# CESC16_copy_copy.net
KiCad netlist of a schematic drawn in EasyEDA
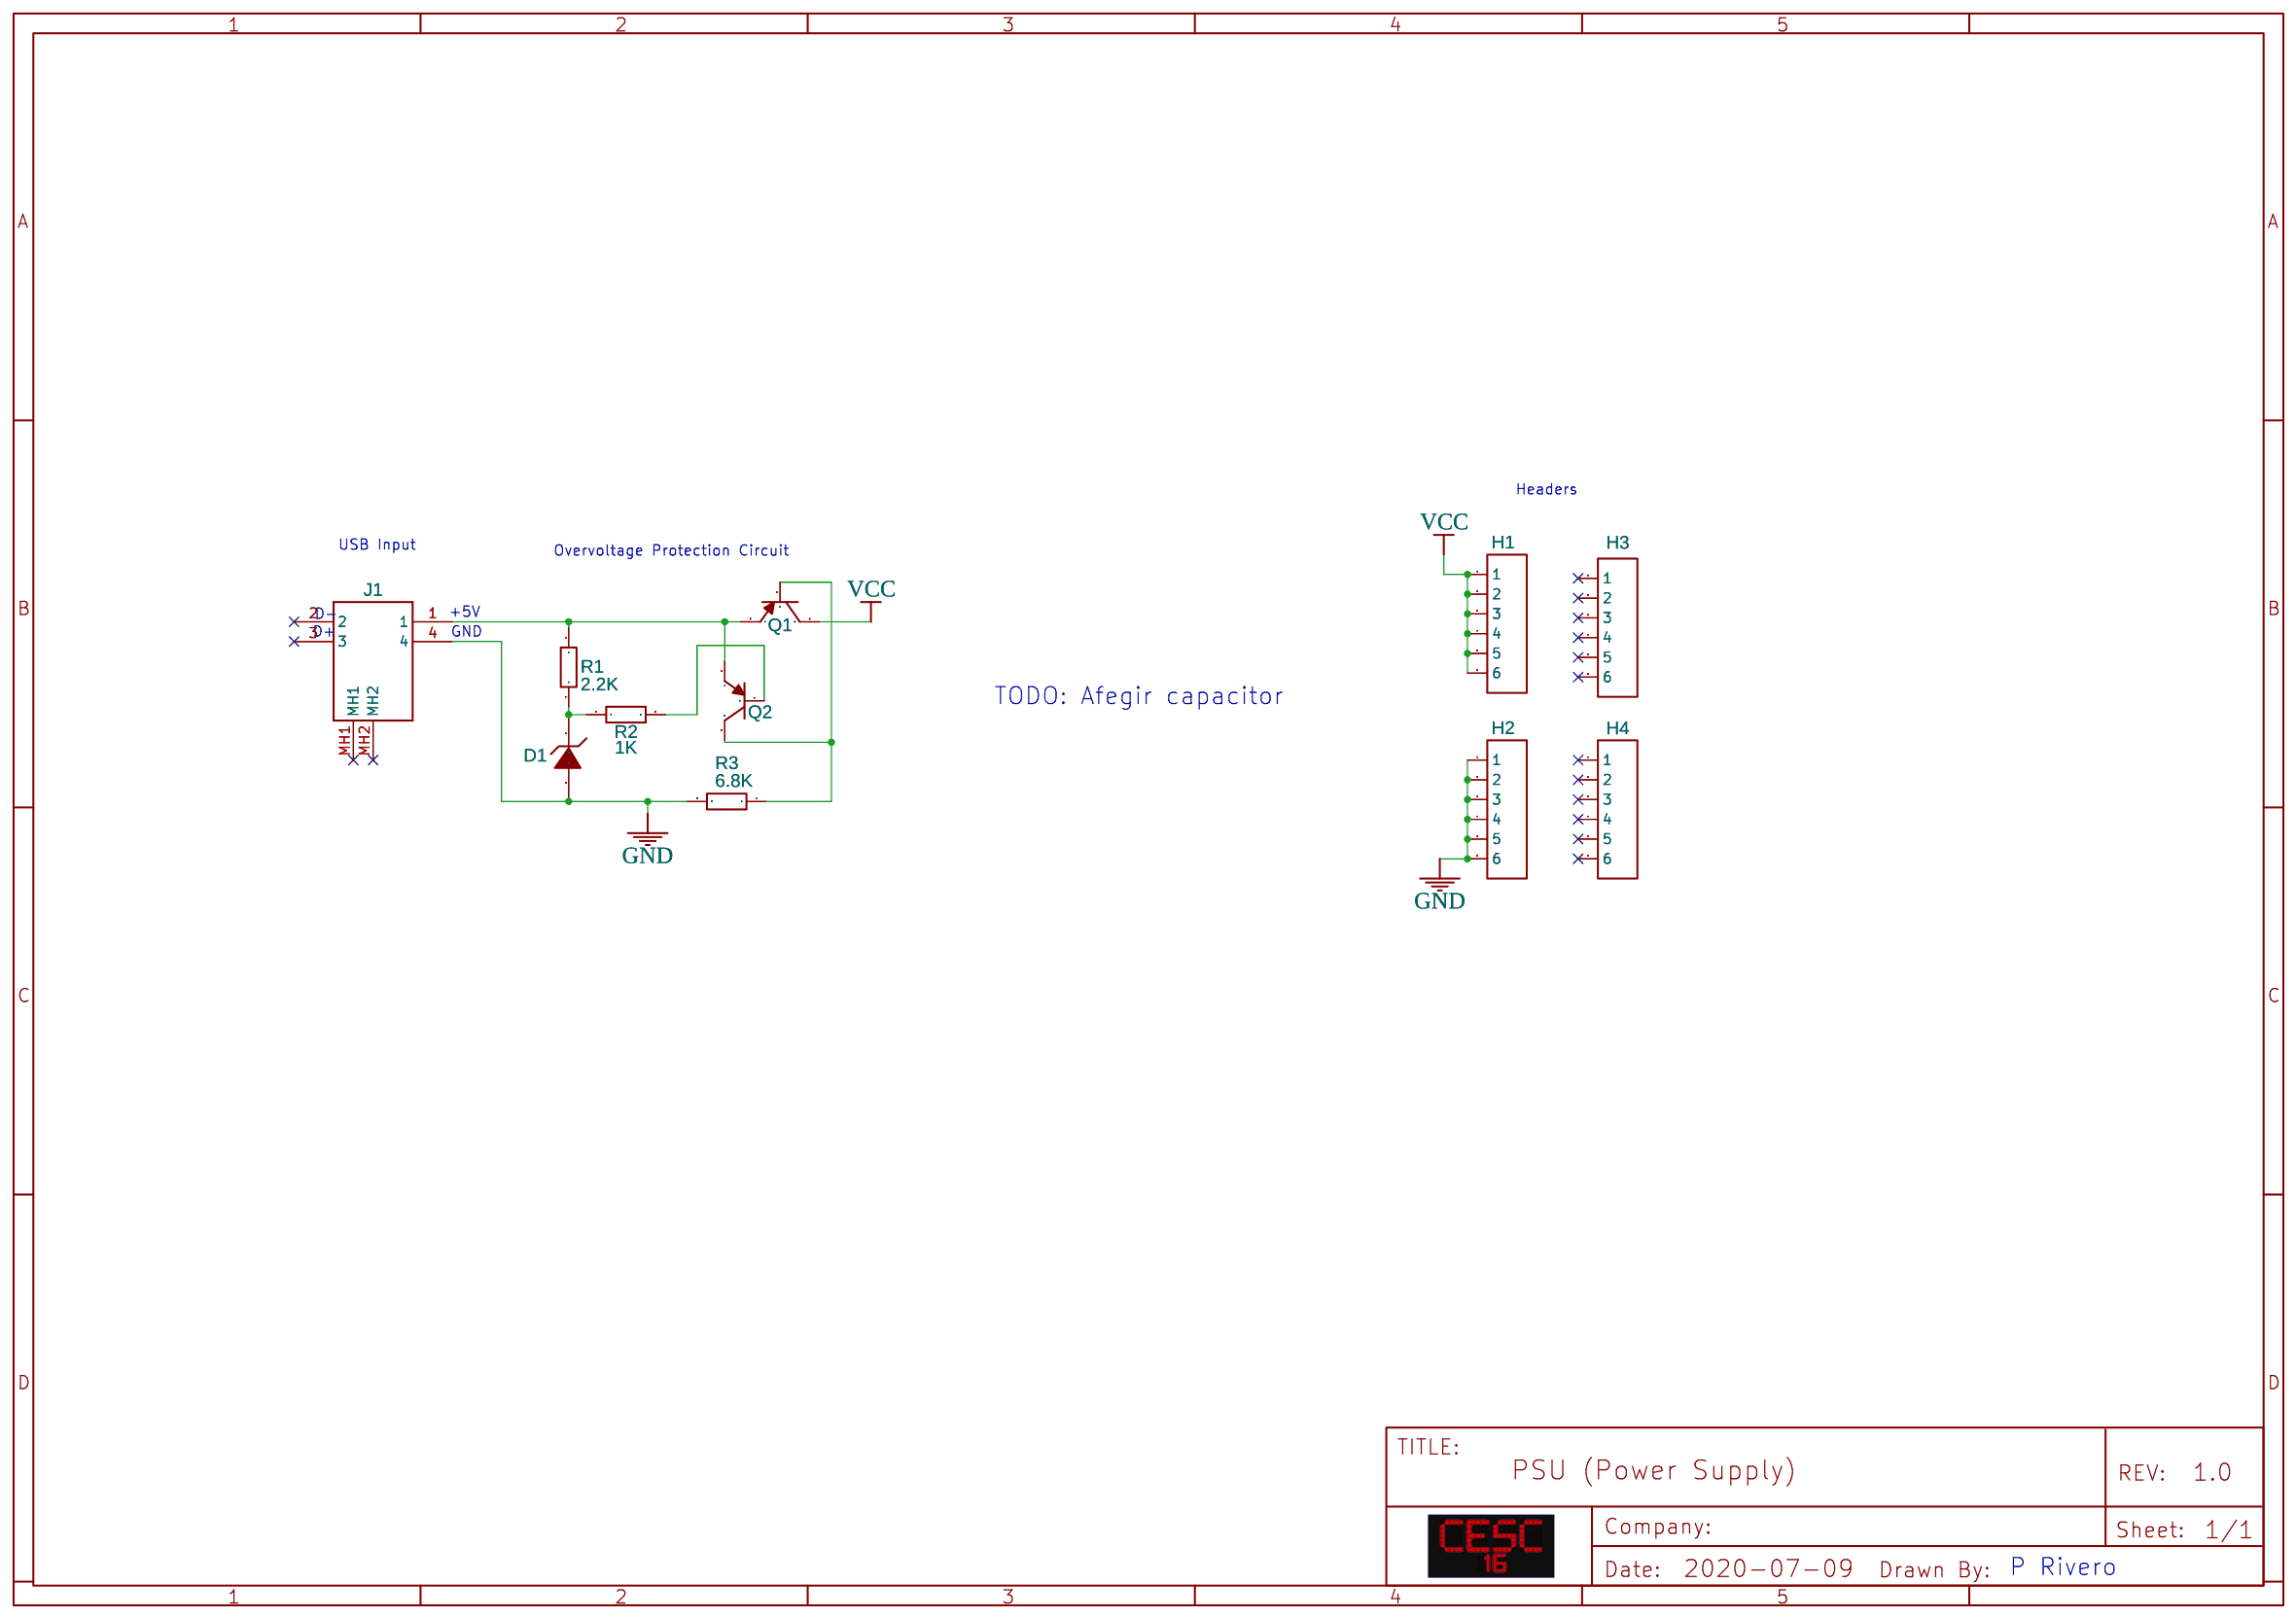
[diagram p0: PSU]
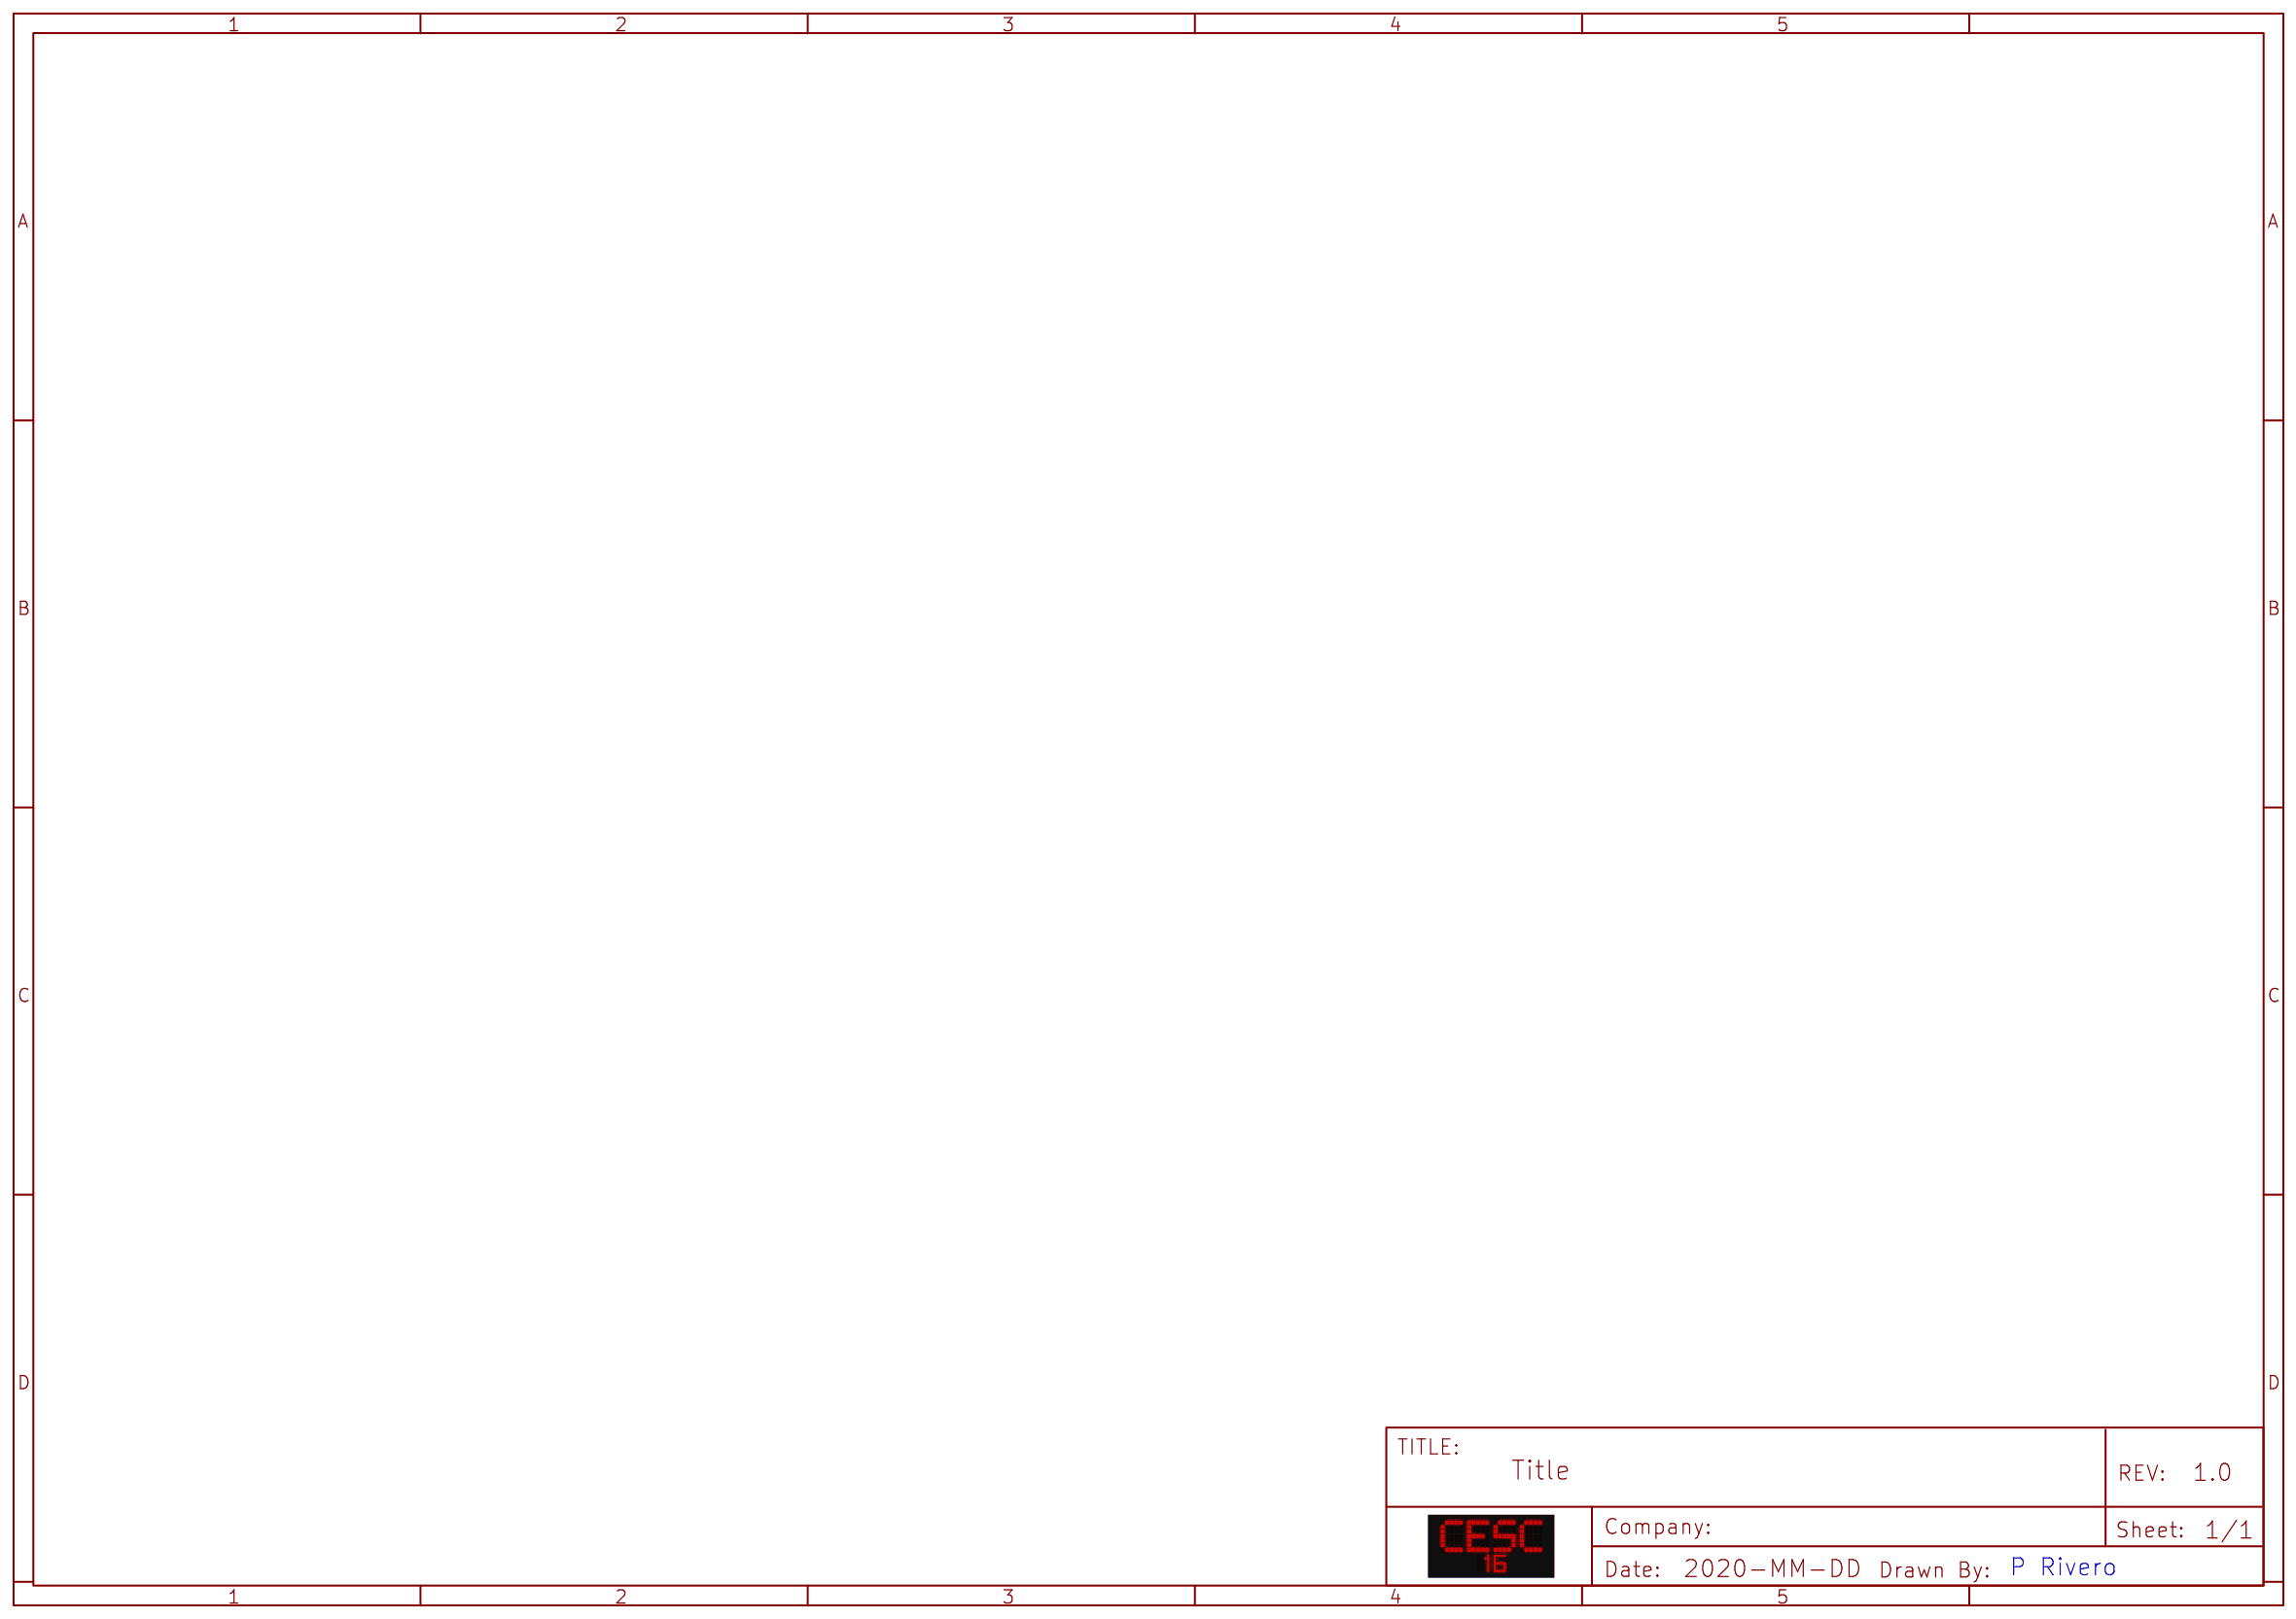
[diagram p1: _Template]
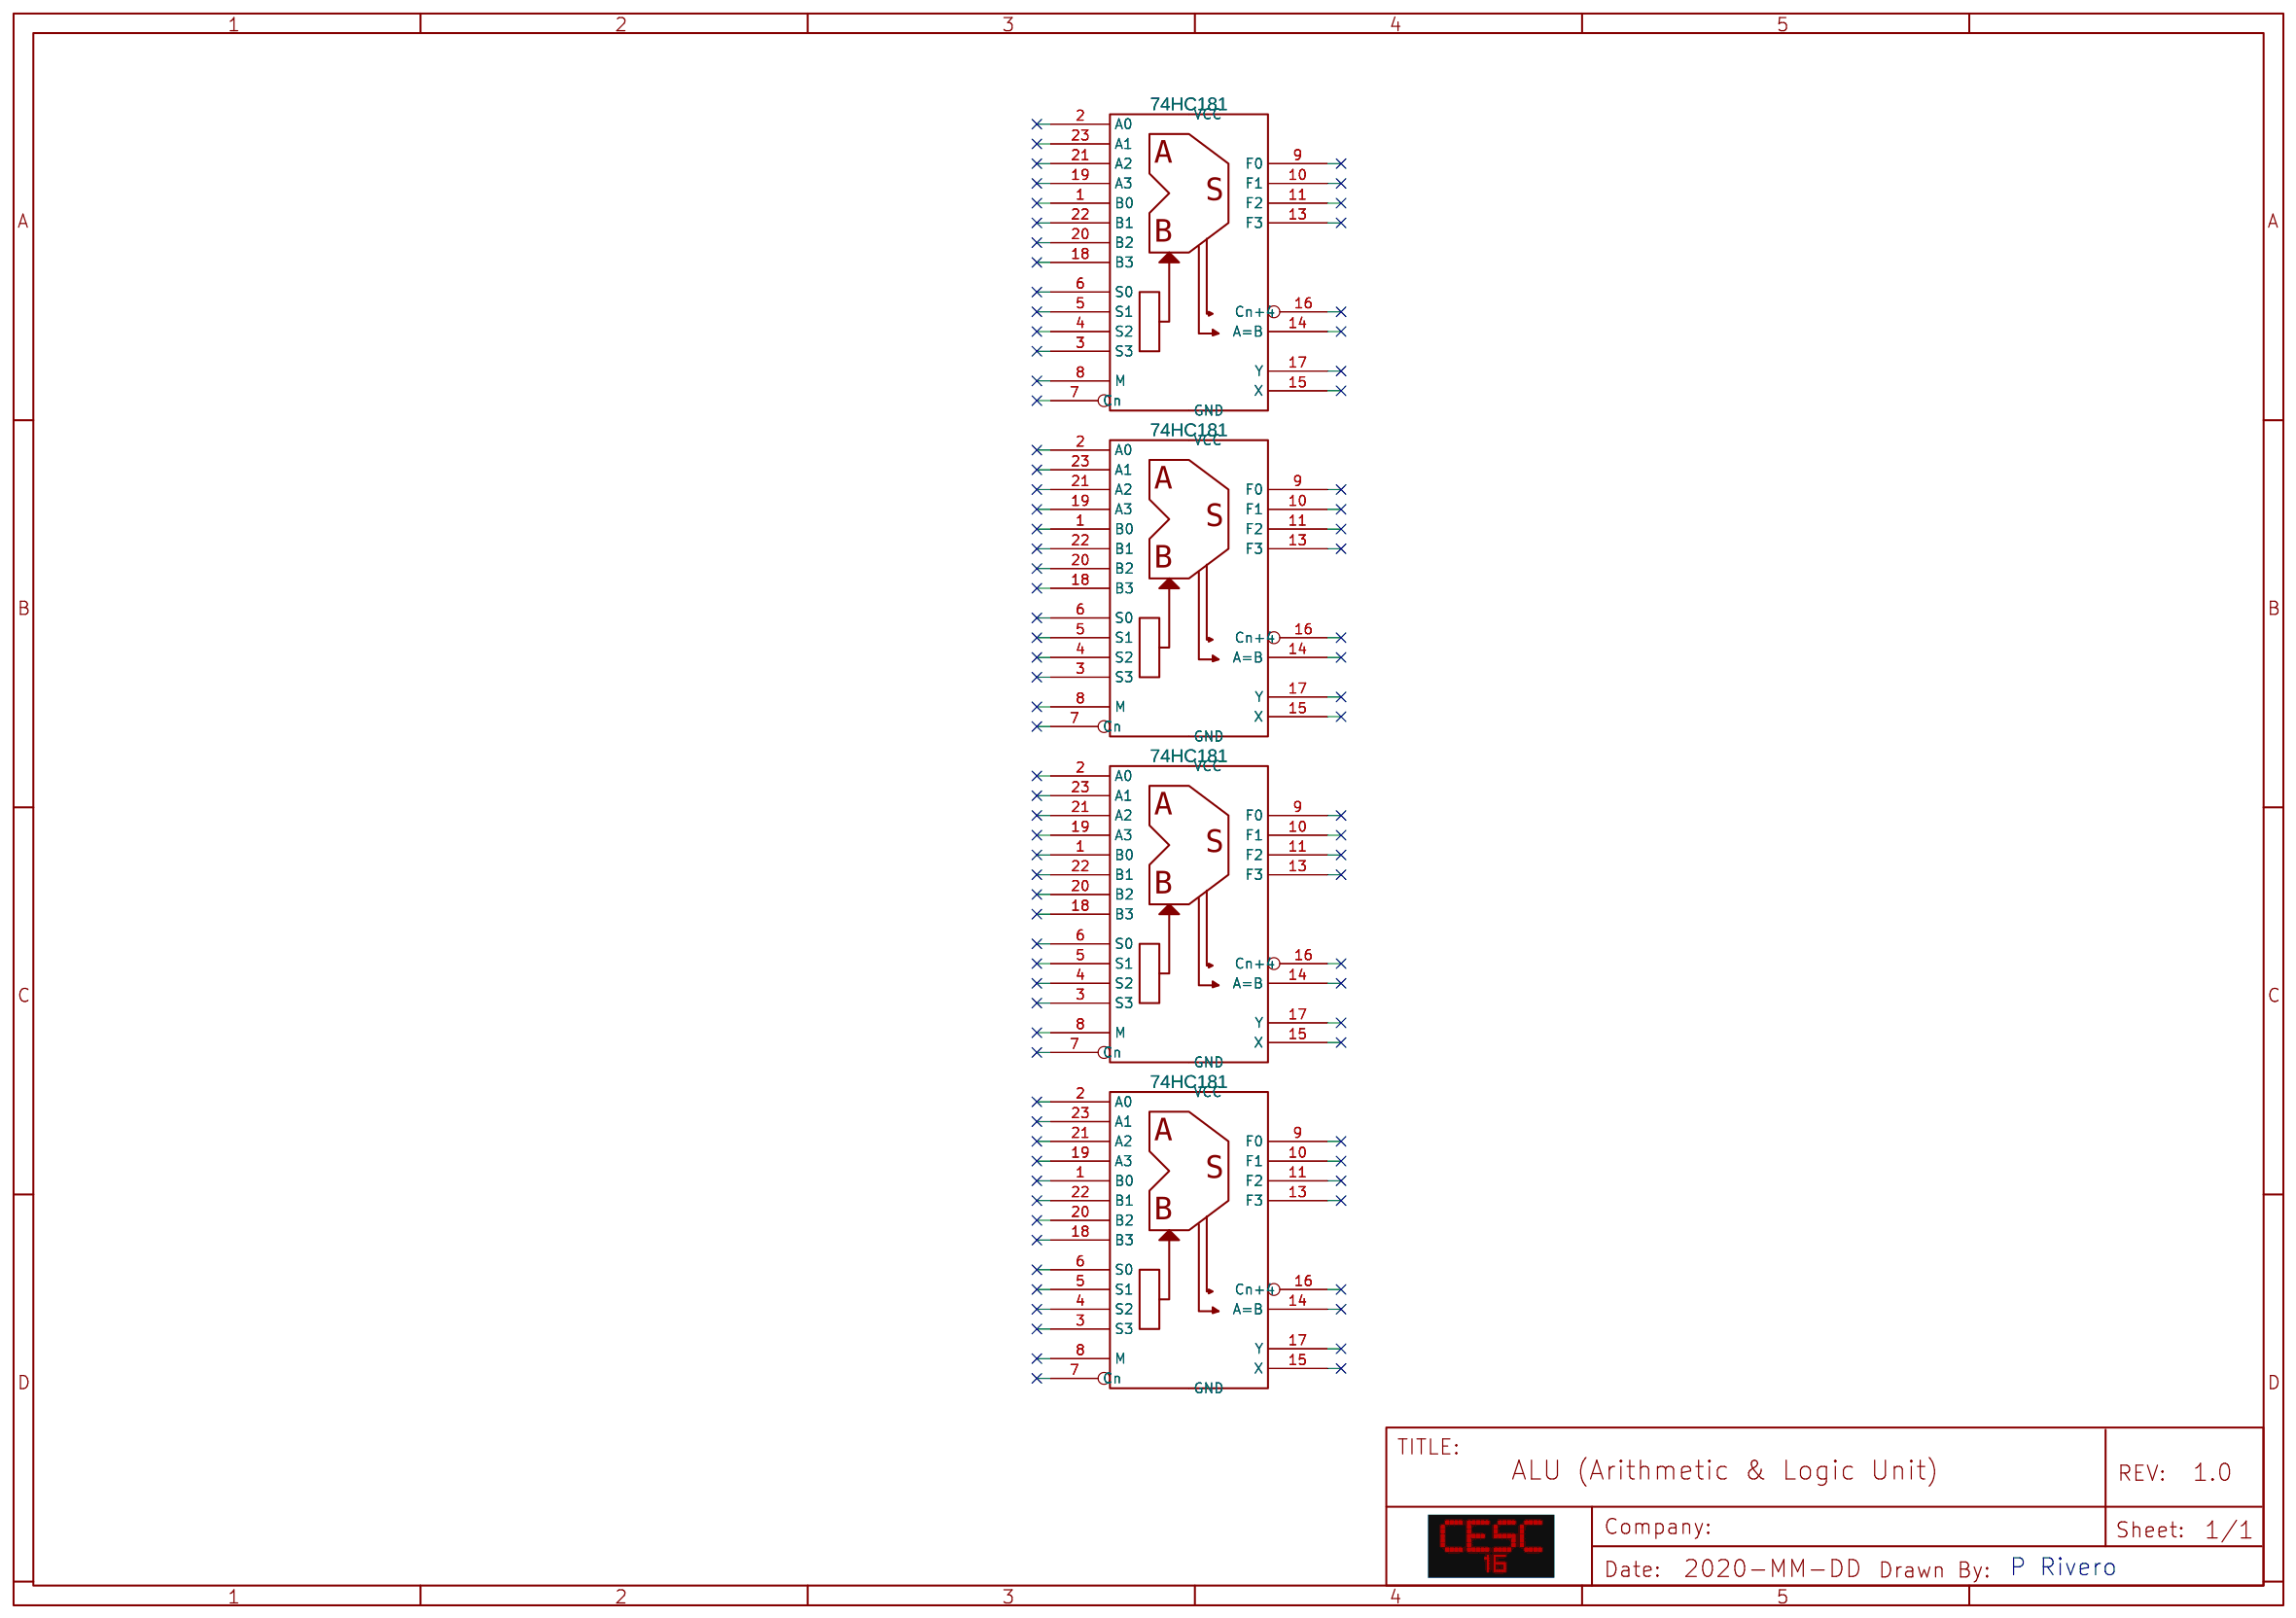
[diagram p2: ALU]
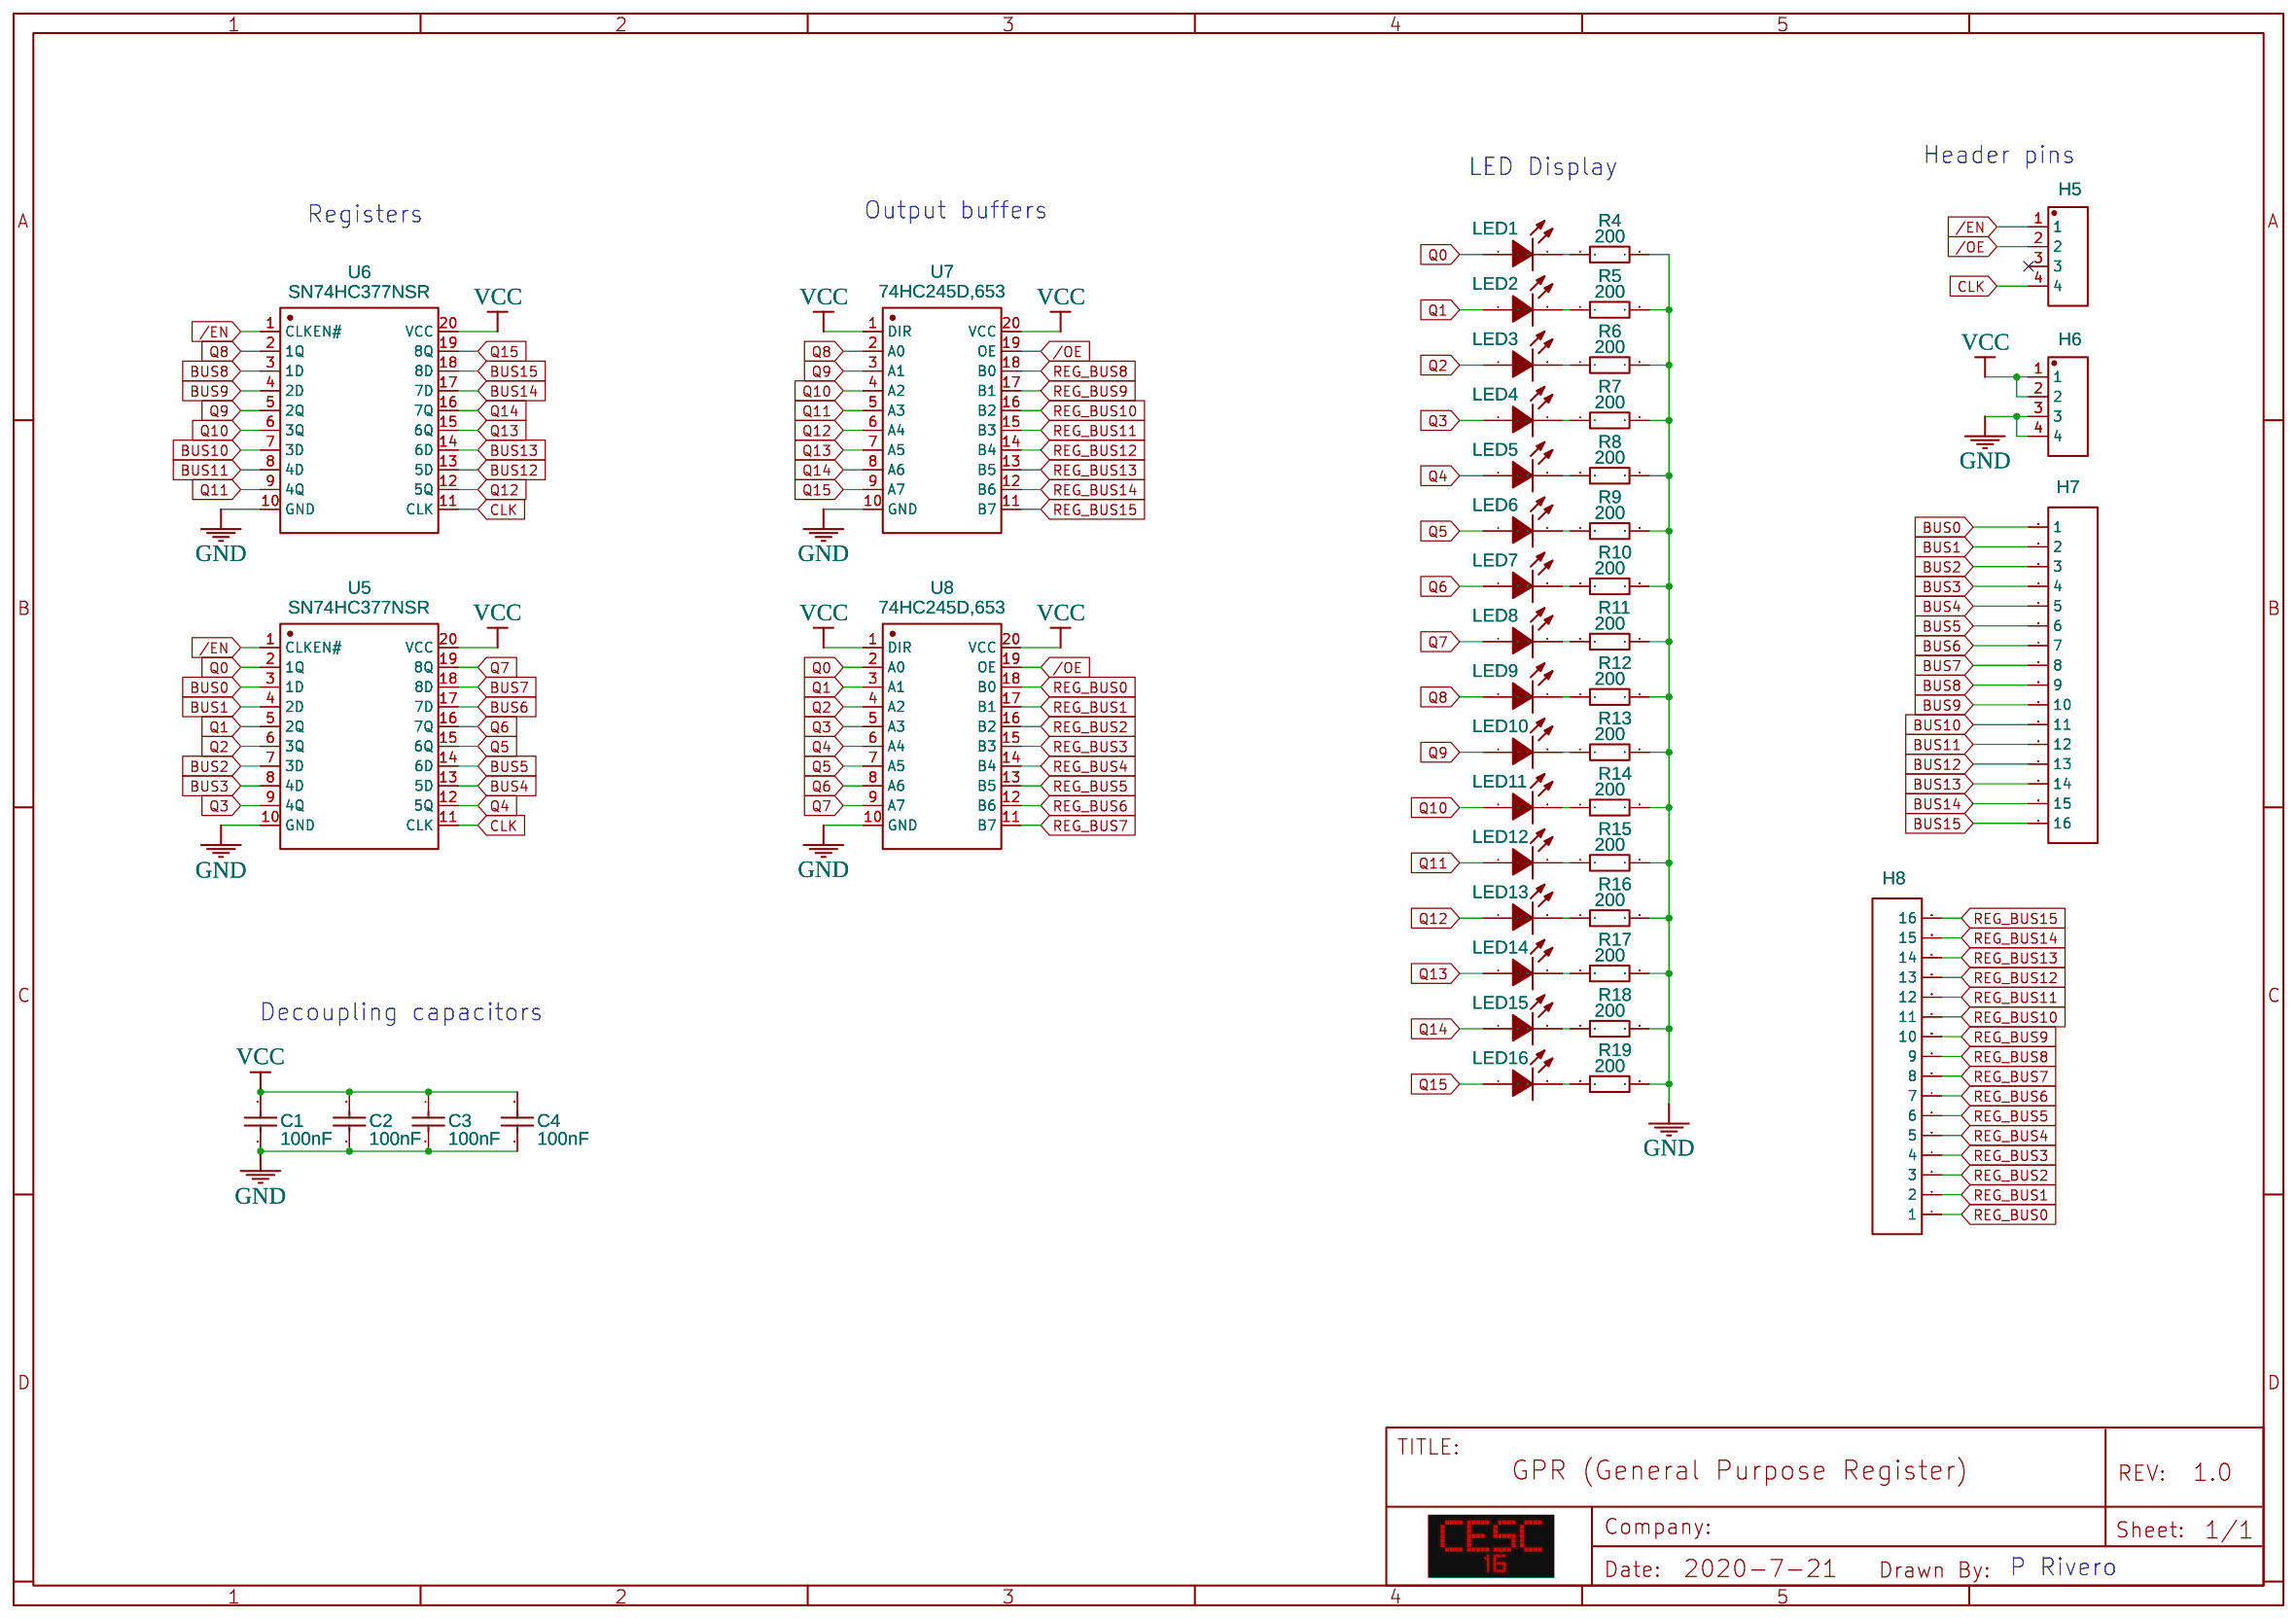
[diagram p3: GPR]

(export (version "E")
  (design (tool "Eeschema 10.0.6"))
  (components
    (comp (ref "D1")
      (value "ZMM5V6")
      (fields (field (name "BOM_Supplier Part") "C8062"))
      (libsource (lib "") (part "ZMM5V6"))
    )
    (comp (ref "H1")
      (value "Header-Male-2.54_1x6")
      (fields (field (name "BOM_Supplier Part") "C37208"))
      (libsource (lib "") (part "Header-Male-2.54_1x6"))
    )
    (comp (ref "H2")
      (value "Header-Male-2.54_1x6")
      (fields (field (name "BOM_Supplier Part") "C37208"))
      (libsource (lib "") (part "Header-Male-2.54_1x6"))
    )
    (comp (ref "H3")
      (value "Header-Male-2.54_1x6")
      (fields (field (name "BOM_Supplier Part") "C37208"))
      (libsource (lib "") (part "Header-Male-2.54_1x6"))
    )
    (comp (ref "H4")
      (value "Header-Male-2.54_1x6")
      (fields (field (name "BOM_Supplier Part") "C37208"))
      (libsource (lib "") (part "Header-Male-2.54_1x6"))
    )
    (comp (ref "J1") (value "UJ2-BH-1-TH") (libsource (lib "") (part "UJ2-BH-1-TH")))
    (comp (ref "Q1")
      (value "S9012 2T1")
      (fields (field (name "BOM_Supplier Part") "C8543"))
      (libsource (lib "") (part "S9012 2T1_1"))
    )
    (comp (ref "Q2")
      (value "S9012 2T1")
      (fields (field (name "BOM_Supplier Part") "C8543"))
      (libsource (lib "") (part "S9012 2T1"))
    )
    (comp (ref "R1")
      (value "2.2K")
      (fields
        (field (name "BOM_Manufacturer Part") "0603WAF2201T5E")
        (field (name "BOM_Supplier Part") "C4190")
      )
      (libsource (lib "") (part "0603WAF2201T5E"))
    )
    (comp (ref "R2")
      (value "1K")
      (fields
        (field (name "BOM_Manufacturer Part") "0402WGF1001TCE")
        (field (name "BOM_Supplier Part") "C11702")
      )
      (libsource (lib "") (part "0402WGF1001TCE"))
    )
    (comp (ref "R3")
      (value "6.8K")
      (fields
        (field (name "BOM_Manufacturer Part") "0402WGF6801TCE")
        (field (name "BOM_Supplier Part") "C25917")
      )
      (libsource (lib "") (part "0402WGF6801TCE"))
    )
    (comp (ref "U1") (value "74HC181") (libsource (lib "") (part "74LS181")))
    (comp (ref "U2") (value "74HC181") (libsource (lib "") (part "74LS181")))
    (comp (ref "U3") (value "74HC181") (libsource (lib "") (part "74LS181")))
    (comp (ref "U4") (value "74HC181") (libsource (lib "") (part "74LS181")))
    (comp (ref "C1")
      (value "100nF")
      (fields
        (field (name "BOM_Manufacturer Part") "CL05B104KO5NNNC")
        (field (name "BOM_Supplier Part") "C1525")
      )
      (libsource (lib "") (part "CL05B104KO5NNNC"))
    )
    (comp (ref "C2")
      (value "100nF")
      (fields
        (field (name "BOM_Manufacturer Part") "CL05B104KO5NNNC")
        (field (name "BOM_Supplier Part") "C1525")
      )
      (libsource (lib "") (part "CL05B104KO5NNNC"))
    )
    (comp (ref "C3")
      (value "100nF")
      (fields
        (field (name "BOM_Manufacturer Part") "CL05B104KO5NNNC")
        (field (name "BOM_Supplier Part") "C1525")
      )
      (libsource (lib "") (part "CL05B104KO5NNNC"))
    )
    (comp (ref "C4")
      (value "100nF")
      (fields
        (field (name "BOM_Manufacturer Part") "CL05B104KO5NNNC")
        (field (name "BOM_Supplier Part") "C1525")
      )
      (libsource (lib "") (part "CL05B104KO5NNNC"))
    )
    (comp (ref "H5")
      (value "Header-Male-2.54_1x4_C59481")
      (fields
        (field (name "BOM_Manufacturer Part") "Headers  Pins 1*4P")
        (field (name "BOM_Supplier Part") "C59481")
      )
      (libsource (lib "") (part "Header-Male-2.54_1x4_C59481"))
    )
    (comp (ref "H6")
      (value "Header-Male-2.54_1x4_C59481")
      (fields
        (field (name "BOM_Manufacturer Part") "Headers  Pins 1*4P")
        (field (name "BOM_Supplier Part") "C59481")
      )
      (libsource (lib "") (part "Header-Male-2.54_1x4_C59481"))
    )
    (comp (ref "H7")
      (value "Header-Female-2.54_1x16")
      (fields
        (field (name "BOM_Manufacturer Part") "Female header1*16P pitch 2.54mm")
        (field (name "BOM_Supplier Part") "C66987")
      )
      (libsource (lib "") (part "Header-Female-2.54_1x16_1"))
    )
    (comp (ref "H8")
      (value "Header-Female-2.54_1x16")
      (fields
        (field (name "BOM_Manufacturer Part") "Female header1*16P pitch 2.54mm")
        (field (name "BOM_Supplier Part") "C66987")
      )
      (libsource (lib "") (part "Header-Female-2.54_1x16"))
    )
    (comp (ref "LED1")
      (value "KT-0603R")
      (fields (field (name "BOM_Supplier Part") "C2286"))
      (libsource (lib "") (part "KT-0603R"))
    )
    (comp (ref "LED2")
      (value "KT-0603R")
      (fields (field (name "BOM_Supplier Part") "C2286"))
      (libsource (lib "") (part "KT-0603R"))
    )
    (comp (ref "LED3")
      (value "KT-0603R")
      (fields (field (name "BOM_Supplier Part") "C2286"))
      (libsource (lib "") (part "KT-0603R"))
    )
    (comp (ref "LED4")
      (value "KT-0603R")
      (fields (field (name "BOM_Supplier Part") "C2286"))
      (libsource (lib "") (part "KT-0603R"))
    )
    (comp (ref "LED5")
      (value "KT-0603R")
      (fields (field (name "BOM_Supplier Part") "C2286"))
      (libsource (lib "") (part "KT-0603R"))
    )
    (comp (ref "LED6")
      (value "KT-0603R")
      (fields (field (name "BOM_Supplier Part") "C2286"))
      (libsource (lib "") (part "KT-0603R"))
    )
    (comp (ref "LED7")
      (value "KT-0603R")
      (fields (field (name "BOM_Supplier Part") "C2286"))
      (libsource (lib "") (part "KT-0603R"))
    )
    (comp (ref "LED8")
      (value "KT-0603R")
      (fields (field (name "BOM_Supplier Part") "C2286"))
      (libsource (lib "") (part "KT-0603R"))
    )
    (comp (ref "LED9")
      (value "KT-0603R")
      (fields (field (name "BOM_Supplier Part") "C2286"))
      (libsource (lib "") (part "KT-0603R"))
    )
    (comp (ref "LED10")
      (value "KT-0603R")
      (fields (field (name "BOM_Supplier Part") "C2286"))
      (libsource (lib "") (part "KT-0603R"))
    )
    (comp (ref "LED11")
      (value "KT-0603R")
      (fields (field (name "BOM_Supplier Part") "C2286"))
      (libsource (lib "") (part "KT-0603R"))
    )
    (comp (ref "LED12")
      (value "KT-0603R")
      (fields (field (name "BOM_Supplier Part") "C2286"))
      (libsource (lib "") (part "KT-0603R"))
    )
    (comp (ref "LED13")
      (value "KT-0603R")
      (fields (field (name "BOM_Supplier Part") "C2286"))
      (libsource (lib "") (part "KT-0603R"))
    )
    (comp (ref "LED14")
      (value "KT-0603R")
      (fields (field (name "BOM_Supplier Part") "C2286"))
      (libsource (lib "") (part "KT-0603R"))
    )
    (comp (ref "LED15")
      (value "KT-0603R")
      (fields (field (name "BOM_Supplier Part") "C2286"))
      (libsource (lib "") (part "KT-0603R"))
    )
    (comp (ref "LED16")
      (value "KT-0603R")
      (fields (field (name "BOM_Supplier Part") "C2286"))
      (libsource (lib "") (part "KT-0603R"))
    )
    (comp (ref "R4")
      (value "200")
      (fields
        (field (name "BOM_Manufacturer Part") "0603WAF2000T5E")
        (field (name "BOM_Supplier Part") "C8218")
      )
      (libsource (lib "") (part "0603WAF2000T5E"))
    )
    (comp (ref "R5")
      (value "200")
      (fields
        (field (name "BOM_Manufacturer Part") "0603WAF2000T5E")
        (field (name "BOM_Supplier Part") "C8218")
      )
      (libsource (lib "") (part "0603WAF2000T5E"))
    )
    (comp (ref "R6")
      (value "200")
      (fields
        (field (name "BOM_Manufacturer Part") "0603WAF2000T5E")
        (field (name "BOM_Supplier Part") "C8218")
      )
      (libsource (lib "") (part "0603WAF2000T5E"))
    )
    (comp (ref "R7")
      (value "200")
      (fields
        (field (name "BOM_Manufacturer Part") "0603WAF2000T5E")
        (field (name "BOM_Supplier Part") "C8218")
      )
      (libsource (lib "") (part "0603WAF2000T5E"))
    )
    (comp (ref "R8")
      (value "200")
      (fields
        (field (name "BOM_Manufacturer Part") "0603WAF2000T5E")
        (field (name "BOM_Supplier Part") "C8218")
      )
      (libsource (lib "") (part "0603WAF2000T5E"))
    )
    (comp (ref "R9")
      (value "200")
      (fields
        (field (name "BOM_Manufacturer Part") "0603WAF2000T5E")
        (field (name "BOM_Supplier Part") "C8218")
      )
      (libsource (lib "") (part "0603WAF2000T5E"))
    )
    (comp (ref "R10")
      (value "200")
      (fields
        (field (name "BOM_Manufacturer Part") "0603WAF2000T5E")
        (field (name "BOM_Supplier Part") "C8218")
      )
      (libsource (lib "") (part "0603WAF2000T5E"))
    )
    (comp (ref "R11")
      (value "200")
      (fields
        (field (name "BOM_Manufacturer Part") "0603WAF2000T5E")
        (field (name "BOM_Supplier Part") "C8218")
      )
      (libsource (lib "") (part "0603WAF2000T5E"))
    )
    (comp (ref "R12")
      (value "200")
      (fields
        (field (name "BOM_Manufacturer Part") "0603WAF2000T5E")
        (field (name "BOM_Supplier Part") "C8218")
      )
      (libsource (lib "") (part "0603WAF2000T5E"))
    )
    (comp (ref "R13")
      (value "200")
      (fields
        (field (name "BOM_Manufacturer Part") "0603WAF2000T5E")
        (field (name "BOM_Supplier Part") "C8218")
      )
      (libsource (lib "") (part "0603WAF2000T5E"))
    )
    (comp (ref "R14")
      (value "200")
      (fields
        (field (name "BOM_Manufacturer Part") "0603WAF2000T5E")
        (field (name "BOM_Supplier Part") "C8218")
      )
      (libsource (lib "") (part "0603WAF2000T5E"))
    )
    (comp (ref "R15")
      (value "200")
      (fields
        (field (name "BOM_Manufacturer Part") "0603WAF2000T5E")
        (field (name "BOM_Supplier Part") "C8218")
      )
      (libsource (lib "") (part "0603WAF2000T5E"))
    )
    (comp (ref "R16")
      (value "200")
      (fields
        (field (name "BOM_Manufacturer Part") "0603WAF2000T5E")
        (field (name "BOM_Supplier Part") "C8218")
      )
      (libsource (lib "") (part "0603WAF2000T5E"))
    )
    (comp (ref "R17")
      (value "200")
      (fields
        (field (name "BOM_Manufacturer Part") "0603WAF2000T5E")
        (field (name "BOM_Supplier Part") "C8218")
      )
      (libsource (lib "") (part "0603WAF2000T5E"))
    )
    (comp (ref "R18")
      (value "200")
      (fields
        (field (name "BOM_Manufacturer Part") "0603WAF2000T5E")
        (field (name "BOM_Supplier Part") "C8218")
      )
      (libsource (lib "") (part "0603WAF2000T5E"))
    )
    (comp (ref "R19")
      (value "200")
      (fields
        (field (name "BOM_Manufacturer Part") "0603WAF2000T5E")
        (field (name "BOM_Supplier Part") "C8218")
      )
      (libsource (lib "") (part "0603WAF2000T5E"))
    )
    (comp (ref "U5")
      (value "SN74HC377NSR")
      (fields (field (name "BOM_Supplier Part") "C7647"))
      (libsource (lib "") (part "SN74HC377NSR"))
    )
    (comp (ref "U6")
      (value "SN74HC377NSR")
      (fields (field (name "BOM_Supplier Part") "C7647"))
      (libsource (lib "") (part "SN74HC377NSR"))
    )
    (comp (ref "U7")
      (value "74HC245D,653")
      (fields (field (name "BOM_Supplier Part") "C5625"))
      (libsource (lib "") (part "74HC245D,653"))
    )
    (comp (ref "U8")
      (value "74HC245D,653")
      (fields (field (name "BOM_Supplier Part") "C5625"))
      (libsource (lib "") (part "74HC245D,653"))
    )
  )
  (nets
    (net (code "1") (name "BUS0") (class "Default")
      (node (ref "H7") (pin "1") (pinfunction "1_1") (pintype "input"))
      (node (ref "U5") (pin "3") (pinfunction "1D_3") (pintype "unspecified"))
    )
    (net (code "2") (name "BUS1") (class "Default")
      (node (ref "H7") (pin "2") (pinfunction "2_2") (pintype "input"))
      (node (ref "U5") (pin "4") (pinfunction "2D_4") (pintype "unspecified"))
    )
    (net (code "3") (name "BUS2") (class "Default")
      (node (ref "H7") (pin "3") (pinfunction "3_3") (pintype "input"))
      (node (ref "U5") (pin "7") (pinfunction "3D_7") (pintype "unspecified"))
    )
    (net (code "4") (name "BUS3") (class "Default")
      (node (ref "H7") (pin "4") (pinfunction "4_4") (pintype "input"))
      (node (ref "U5") (pin "8") (pinfunction "4D_8") (pintype "unspecified"))
    )
    (net (code "5") (name "BUS4") (class "Default")
      (node (ref "H7") (pin "5") (pinfunction "5_5") (pintype "input"))
      (node (ref "U5") (pin "13") (pinfunction "5D_13") (pintype "unspecified"))
    )
    (net (code "6") (name "BUS5") (class "Default")
      (node (ref "H7") (pin "6") (pinfunction "6_6") (pintype "input"))
      (node (ref "U5") (pin "14") (pinfunction "6D_14") (pintype "unspecified"))
    )
    (net (code "7") (name "BUS6") (class "Default")
      (node (ref "H7") (pin "7") (pinfunction "7_7") (pintype "input"))
      (node (ref "U5") (pin "17") (pinfunction "7D_17") (pintype "unspecified"))
    )
    (net (code "8") (name "BUS7") (class "Default")
      (node (ref "H7") (pin "8") (pinfunction "8_8") (pintype "input"))
      (node (ref "U5") (pin "18") (pinfunction "8D_18") (pintype "unspecified"))
    )
    (net (code "9") (name "BUS8") (class "Default")
      (node (ref "H7") (pin "9") (pinfunction "9_9") (pintype "input"))
      (node (ref "U6") (pin "3") (pinfunction "1D_3") (pintype "unspecified"))
    )
    (net (code "10") (name "BUS9") (class "Default")
      (node (ref "H7") (pin "10") (pinfunction "10_10") (pintype "input"))
      (node (ref "U6") (pin "4") (pinfunction "2D_4") (pintype "unspecified"))
    )
    (net (code "11") (name "BUS10") (class "Default")
      (node (ref "H7") (pin "11") (pinfunction "11_11") (pintype "input"))
      (node (ref "U6") (pin "7") (pinfunction "3D_7") (pintype "unspecified"))
    )
    (net (code "12") (name "BUS11") (class "Default")
      (node (ref "H7") (pin "12") (pinfunction "12_12") (pintype "input"))
      (node (ref "U6") (pin "8") (pinfunction "4D_8") (pintype "unspecified"))
    )
    (net (code "13") (name "BUS12") (class "Default")
      (node (ref "H7") (pin "13") (pinfunction "13_13") (pintype "input"))
      (node (ref "U6") (pin "13") (pinfunction "5D_13") (pintype "unspecified"))
    )
    (net (code "14") (name "BUS13") (class "Default")
      (node (ref "H7") (pin "14") (pinfunction "14_14") (pintype "input"))
      (node (ref "U6") (pin "14") (pinfunction "6D_14") (pintype "unspecified"))
    )
    (net (code "15") (name "BUS14") (class "Default")
      (node (ref "H7") (pin "15") (pinfunction "15_15") (pintype "input"))
      (node (ref "U6") (pin "17") (pinfunction "7D_17") (pintype "unspecified"))
    )
    (net (code "16") (name "BUS15") (class "Default")
      (node (ref "H7") (pin "16") (pinfunction "16_16") (pintype "input"))
      (node (ref "U6") (pin "18") (pinfunction "8D_18") (pintype "unspecified"))
    )
    (net (code "17") (name "CLK") (class "Default")
      (node (ref "H5") (pin "4") (pinfunction "4_4") (pintype "unspecified"))
      (node (ref "U5") (pin "11") (pinfunction "CLK_11") (pintype "unspecified"))
      (node (ref "U6") (pin "11") (pinfunction "CLK_11") (pintype "unspecified"))
    )
    (net (code "18") (name "GND") (class "Default")
      (node (ref "C1") (pin "2") (pinfunction "2_2") (pintype "input"))
      (node (ref "C2") (pin "2") (pinfunction "2_2") (pintype "input"))
      (node (ref "C3") (pin "2") (pinfunction "2_2") (pintype "input"))
      (node (ref "C4") (pin "2") (pinfunction "2_2") (pintype "input"))
      (node (ref "D1") (pin "2") (pinfunction "A_2") (pintype "unspecified"))
      (node (ref "H2") (pin "1") (pinfunction "1_1") (pintype "input"))
      (node (ref "H2") (pin "2") (pinfunction "2_2") (pintype "input"))
      (node (ref "H2") (pin "3") (pinfunction "3_3") (pintype "input"))
      (node (ref "H2") (pin "4") (pinfunction "4_4") (pintype "input"))
      (node (ref "H2") (pin "5") (pinfunction "5_5") (pintype "input"))
      (node (ref "H2") (pin "6") (pinfunction "6_6") (pintype "input"))
      (node (ref "H6") (pin "3") (pinfunction "3_3") (pintype "unspecified"))
      (node (ref "H6") (pin "4") (pinfunction "4_4") (pintype "unspecified"))
      (node (ref "J1") (pin "4") (pinfunction "4_4") (pintype "bidirectional"))
      (node (ref "R10") (pin "2") (pinfunction "2_2") (pintype "input"))
      (node (ref "R11") (pin "2") (pinfunction "2_2") (pintype "input"))
      (node (ref "R12") (pin "2") (pinfunction "2_2") (pintype "input"))
      (node (ref "R13") (pin "2") (pinfunction "2_2") (pintype "input"))
      (node (ref "R14") (pin "2") (pinfunction "2_2") (pintype "input"))
      (node (ref "R15") (pin "2") (pinfunction "2_2") (pintype "input"))
      (node (ref "R16") (pin "2") (pinfunction "2_2") (pintype "input"))
      (node (ref "R17") (pin "2") (pinfunction "2_2") (pintype "input"))
      (node (ref "R18") (pin "2") (pinfunction "2_2") (pintype "input"))
      (node (ref "R19") (pin "2") (pinfunction "2_2") (pintype "input"))
      (node (ref "R3") (pin "2") (pinfunction "2_2") (pintype "input"))
      (node (ref "R4") (pin "2") (pinfunction "2_2") (pintype "input"))
      (node (ref "R5") (pin "2") (pinfunction "2_2") (pintype "input"))
      (node (ref "R6") (pin "2") (pinfunction "2_2") (pintype "input"))
      (node (ref "R7") (pin "2") (pinfunction "2_2") (pintype "input"))
      (node (ref "R8") (pin "2") (pinfunction "2_2") (pintype "input"))
      (node (ref "R9") (pin "2") (pinfunction "2_2") (pintype "input"))
      (node (ref "U5") (pin "10") (pinfunction "GND_10") (pintype "unspecified"))
      (node (ref "U6") (pin "10") (pinfunction "GND_10") (pintype "unspecified"))
      (node (ref "U7") (pin "10") (pinfunction "GND_10") (pintype "unspecified"))
      (node (ref "U8") (pin "10") (pinfunction "GND_10") (pintype "unspecified"))
    )
    (net (code "19") (name "Net-(D1-C)") (class "Default")
      (node (ref "D1") (pin "1") (pinfunction "C_1") (pintype "unspecified"))
      (node (ref "R1") (pin "2") (pinfunction "2_2") (pintype "input"))
      (node (ref "R2") (pin "1") (pinfunction "1_1") (pintype "input"))
    )
    (net (code "20") (name "Net-(LED1-K)") (class "Default")
      (node (ref "LED1") (pin "2") (pinfunction "K_2") (pintype "unspecified"))
      (node (ref "R4") (pin "1") (pinfunction "1_1") (pintype "input"))
    )
    (net (code "21") (name "Net-(LED2-K)") (class "Default")
      (node (ref "LED2") (pin "2") (pinfunction "K_2") (pintype "unspecified"))
      (node (ref "R5") (pin "1") (pinfunction "1_1") (pintype "input"))
    )
    (net (code "22") (name "Net-(LED3-K)") (class "Default")
      (node (ref "LED3") (pin "2") (pinfunction "K_2") (pintype "unspecified"))
      (node (ref "R6") (pin "1") (pinfunction "1_1") (pintype "input"))
    )
    (net (code "23") (name "Net-(LED4-K)") (class "Default")
      (node (ref "LED4") (pin "2") (pinfunction "K_2") (pintype "unspecified"))
      (node (ref "R7") (pin "1") (pinfunction "1_1") (pintype "input"))
    )
    (net (code "24") (name "Net-(LED5-K)") (class "Default")
      (node (ref "LED5") (pin "2") (pinfunction "K_2") (pintype "unspecified"))
      (node (ref "R8") (pin "1") (pinfunction "1_1") (pintype "input"))
    )
    (net (code "25") (name "Net-(LED6-K)") (class "Default")
      (node (ref "LED6") (pin "2") (pinfunction "K_2") (pintype "unspecified"))
      (node (ref "R9") (pin "1") (pinfunction "1_1") (pintype "input"))
    )
    (net (code "26") (name "Net-(LED7-K)") (class "Default")
      (node (ref "LED7") (pin "2") (pinfunction "K_2") (pintype "unspecified"))
      (node (ref "R10") (pin "1") (pinfunction "1_1") (pintype "input"))
    )
    (net (code "27") (name "Net-(LED8-K)") (class "Default")
      (node (ref "LED8") (pin "2") (pinfunction "K_2") (pintype "unspecified"))
      (node (ref "R11") (pin "1") (pinfunction "1_1") (pintype "input"))
    )
    (net (code "28") (name "Net-(LED9-K)") (class "Default")
      (node (ref "LED9") (pin "2") (pinfunction "K_2") (pintype "unspecified"))
      (node (ref "R12") (pin "1") (pinfunction "1_1") (pintype "input"))
    )
    (net (code "29") (name "Net-(LED10-K)") (class "Default")
      (node (ref "LED10") (pin "2") (pinfunction "K_2") (pintype "unspecified"))
      (node (ref "R13") (pin "1") (pinfunction "1_1") (pintype "input"))
    )
    (net (code "30") (name "Net-(LED11-K)") (class "Default")
      (node (ref "LED11") (pin "2") (pinfunction "K_2") (pintype "unspecified"))
      (node (ref "R14") (pin "1") (pinfunction "1_1") (pintype "input"))
    )
    (net (code "31") (name "Net-(LED12-K)") (class "Default")
      (node (ref "LED12") (pin "2") (pinfunction "K_2") (pintype "unspecified"))
      (node (ref "R15") (pin "1") (pinfunction "1_1") (pintype "input"))
    )
    (net (code "32") (name "Net-(LED13-K)") (class "Default")
      (node (ref "LED13") (pin "2") (pinfunction "K_2") (pintype "unspecified"))
      (node (ref "R16") (pin "1") (pinfunction "1_1") (pintype "input"))
    )
    (net (code "33") (name "Net-(LED14-K)") (class "Default")
      (node (ref "LED14") (pin "2") (pinfunction "K_2") (pintype "unspecified"))
      (node (ref "R17") (pin "1") (pinfunction "1_1") (pintype "input"))
    )
    (net (code "34") (name "Net-(LED15-K)") (class "Default")
      (node (ref "LED15") (pin "2") (pinfunction "K_2") (pintype "unspecified"))
      (node (ref "R18") (pin "1") (pinfunction "1_1") (pintype "input"))
    )
    (net (code "35") (name "Net-(LED16-K)") (class "Default")
      (node (ref "LED16") (pin "2") (pinfunction "K_2") (pintype "unspecified"))
      (node (ref "R19") (pin "1") (pinfunction "1_1") (pintype "input"))
    )
    (net (code "36") (name "Net-(Q1-B)") (class "Default")
      (node (ref "Q1") (pin "1") (pinfunction "B_1") (pintype "unspecified"))
      (node (ref "Q2") (pin "3") (pinfunction "C_3") (pintype "unspecified"))
      (node (ref "R3") (pin "1") (pinfunction "1_1") (pintype "input"))
    )
    (net (code "37") (name "Net-(Q1-E)") (class "Default")
      (node (ref "J1") (pin "1") (pinfunction "1_1") (pintype "bidirectional"))
      (node (ref "Q1") (pin "2") (pinfunction "E_2") (pintype "unspecified"))
      (node (ref "Q2") (pin "2") (pinfunction "E_2") (pintype "unspecified"))
      (node (ref "R1") (pin "1") (pinfunction "1_1") (pintype "input"))
    )
    (net (code "38") (name "Net-(Q2-B)") (class "Default")
      (node (ref "Q2") (pin "1") (pinfunction "B_1") (pintype "unspecified"))
      (node (ref "R2") (pin "2") (pinfunction "2_2") (pintype "input"))
    )
    (net (code "39") (name "Q0") (class "Default")
      (node (ref "LED1") (pin "1") (pinfunction "A_1") (pintype "unspecified"))
      (node (ref "U5") (pin "2") (pinfunction "1Q_2") (pintype "unspecified"))
      (node (ref "U8") (pin "2") (pinfunction "A0_2") (pintype "unspecified"))
    )
    (net (code "40") (name "Q1") (class "Default")
      (node (ref "LED2") (pin "1") (pinfunction "A_1") (pintype "unspecified"))
      (node (ref "U5") (pin "5") (pinfunction "2Q_5") (pintype "unspecified"))
      (node (ref "U8") (pin "3") (pinfunction "A1_3") (pintype "unspecified"))
    )
    (net (code "41") (name "Q2") (class "Default")
      (node (ref "LED3") (pin "1") (pinfunction "A_1") (pintype "unspecified"))
      (node (ref "U5") (pin "6") (pinfunction "3Q_6") (pintype "unspecified"))
      (node (ref "U8") (pin "4") (pinfunction "A2_4") (pintype "unspecified"))
    )
    (net (code "42") (name "Q3") (class "Default")
      (node (ref "LED4") (pin "1") (pinfunction "A_1") (pintype "unspecified"))
      (node (ref "U5") (pin "9") (pinfunction "4Q_9") (pintype "unspecified"))
      (node (ref "U8") (pin "5") (pinfunction "A3_5") (pintype "unspecified"))
    )
    (net (code "43") (name "Q4") (class "Default")
      (node (ref "LED5") (pin "1") (pinfunction "A_1") (pintype "unspecified"))
      (node (ref "U5") (pin "12") (pinfunction "5Q_12") (pintype "unspecified"))
      (node (ref "U8") (pin "6") (pinfunction "A4_6") (pintype "unspecified"))
    )
    (net (code "44") (name "Q5") (class "Default")
      (node (ref "LED6") (pin "1") (pinfunction "A_1") (pintype "unspecified"))
      (node (ref "U5") (pin "15") (pinfunction "6Q_15") (pintype "unspecified"))
      (node (ref "U8") (pin "7") (pinfunction "A5_7") (pintype "unspecified"))
    )
    (net (code "45") (name "Q6") (class "Default")
      (node (ref "LED7") (pin "1") (pinfunction "A_1") (pintype "unspecified"))
      (node (ref "U5") (pin "16") (pinfunction "7Q_16") (pintype "unspecified"))
      (node (ref "U8") (pin "8") (pinfunction "A6_8") (pintype "unspecified"))
    )
    (net (code "46") (name "Q7") (class "Default")
      (node (ref "LED8") (pin "1") (pinfunction "A_1") (pintype "unspecified"))
      (node (ref "U5") (pin "19") (pinfunction "8Q_19") (pintype "unspecified"))
      (node (ref "U8") (pin "9") (pinfunction "A7_9") (pintype "unspecified"))
    )
    (net (code "47") (name "Q8") (class "Default")
      (node (ref "LED9") (pin "1") (pinfunction "A_1") (pintype "unspecified"))
      (node (ref "U6") (pin "2") (pinfunction "1Q_2") (pintype "unspecified"))
      (node (ref "U7") (pin "2") (pinfunction "A0_2") (pintype "unspecified"))
    )
    (net (code "48") (name "Q9") (class "Default")
      (node (ref "LED10") (pin "1") (pinfunction "A_1") (pintype "unspecified"))
      (node (ref "U6") (pin "5") (pinfunction "2Q_5") (pintype "unspecified"))
      (node (ref "U7") (pin "3") (pinfunction "A1_3") (pintype "unspecified"))
    )
    (net (code "49") (name "Q10") (class "Default")
      (node (ref "LED11") (pin "1") (pinfunction "A_1") (pintype "unspecified"))
      (node (ref "U6") (pin "6") (pinfunction "3Q_6") (pintype "unspecified"))
      (node (ref "U7") (pin "4") (pinfunction "A2_4") (pintype "unspecified"))
    )
    (net (code "50") (name "Q11") (class "Default")
      (node (ref "LED12") (pin "1") (pinfunction "A_1") (pintype "unspecified"))
      (node (ref "U6") (pin "9") (pinfunction "4Q_9") (pintype "unspecified"))
      (node (ref "U7") (pin "5") (pinfunction "A3_5") (pintype "unspecified"))
    )
    (net (code "51") (name "Q12") (class "Default")
      (node (ref "LED13") (pin "1") (pinfunction "A_1") (pintype "unspecified"))
      (node (ref "U6") (pin "12") (pinfunction "5Q_12") (pintype "unspecified"))
      (node (ref "U7") (pin "6") (pinfunction "A4_6") (pintype "unspecified"))
    )
    (net (code "52") (name "Q13") (class "Default")
      (node (ref "LED14") (pin "1") (pinfunction "A_1") (pintype "unspecified"))
      (node (ref "U6") (pin "15") (pinfunction "6Q_15") (pintype "unspecified"))
      (node (ref "U7") (pin "7") (pinfunction "A5_7") (pintype "unspecified"))
    )
    (net (code "53") (name "Q14") (class "Default")
      (node (ref "LED15") (pin "1") (pinfunction "A_1") (pintype "unspecified"))
      (node (ref "U6") (pin "16") (pinfunction "7Q_16") (pintype "unspecified"))
      (node (ref "U7") (pin "8") (pinfunction "A6_8") (pintype "unspecified"))
    )
    (net (code "54") (name "Q15") (class "Default")
      (node (ref "LED16") (pin "1") (pinfunction "A_1") (pintype "unspecified"))
      (node (ref "U6") (pin "19") (pinfunction "8Q_19") (pintype "unspecified"))
      (node (ref "U7") (pin "9") (pinfunction "A7_9") (pintype "unspecified"))
    )
    (net (code "55") (name "REG_BUS0") (class "Default")
      (node (ref "H8") (pin "1") (pinfunction "1_1") (pintype "input"))
      (node (ref "U8") (pin "18") (pinfunction "B0_18") (pintype "unspecified"))
    )
    (net (code "56") (name "REG_BUS1") (class "Default")
      (node (ref "H8") (pin "2") (pinfunction "2_2") (pintype "input"))
      (node (ref "U8") (pin "17") (pinfunction "B1_17") (pintype "unspecified"))
    )
    (net (code "57") (name "REG_BUS2") (class "Default")
      (node (ref "H8") (pin "3") (pinfunction "3_3") (pintype "input"))
      (node (ref "U8") (pin "16") (pinfunction "B2_16") (pintype "unspecified"))
    )
    (net (code "58") (name "REG_BUS3") (class "Default")
      (node (ref "H8") (pin "4") (pinfunction "4_4") (pintype "input"))
      (node (ref "U8") (pin "15") (pinfunction "B3_15") (pintype "unspecified"))
    )
    (net (code "59") (name "REG_BUS4") (class "Default")
      (node (ref "H8") (pin "5") (pinfunction "5_5") (pintype "input"))
      (node (ref "U8") (pin "14") (pinfunction "B4_14") (pintype "unspecified"))
    )
    (net (code "60") (name "REG_BUS5") (class "Default")
      (node (ref "H8") (pin "6") (pinfunction "6_6") (pintype "input"))
      (node (ref "U8") (pin "13") (pinfunction "B5_13") (pintype "unspecified"))
    )
    (net (code "61") (name "REG_BUS6") (class "Default")
      (node (ref "H8") (pin "7") (pinfunction "7_7") (pintype "input"))
      (node (ref "U8") (pin "12") (pinfunction "B6_12") (pintype "unspecified"))
    )
    (net (code "62") (name "REG_BUS7") (class "Default")
      (node (ref "H8") (pin "8") (pinfunction "8_8") (pintype "input"))
      (node (ref "U8") (pin "11") (pinfunction "B7_11") (pintype "unspecified"))
    )
    (net (code "63") (name "REG_BUS8") (class "Default")
      (node (ref "H8") (pin "9") (pinfunction "9_9") (pintype "input"))
      (node (ref "U7") (pin "18") (pinfunction "B0_18") (pintype "unspecified"))
    )
    (net (code "64") (name "REG_BUS9") (class "Default")
      (node (ref "H8") (pin "10") (pinfunction "10_10") (pintype "input"))
      (node (ref "U7") (pin "17") (pinfunction "B1_17") (pintype "unspecified"))
    )
    (net (code "65") (name "REG_BUS10") (class "Default")
      (node (ref "H8") (pin "11") (pinfunction "11_11") (pintype "input"))
      (node (ref "U7") (pin "16") (pinfunction "B2_16") (pintype "unspecified"))
    )
    (net (code "66") (name "REG_BUS11") (class "Default")
      (node (ref "H8") (pin "12") (pinfunction "12_12") (pintype "input"))
      (node (ref "U7") (pin "15") (pinfunction "B3_15") (pintype "unspecified"))
    )
    (net (code "67") (name "REG_BUS12") (class "Default")
      (node (ref "H8") (pin "13") (pinfunction "13_13") (pintype "input"))
      (node (ref "U7") (pin "14") (pinfunction "B4_14") (pintype "unspecified"))
    )
    (net (code "68") (name "REG_BUS13") (class "Default")
      (node (ref "H8") (pin "14") (pinfunction "14_14") (pintype "input"))
      (node (ref "U7") (pin "13") (pinfunction "B5_13") (pintype "unspecified"))
    )
    (net (code "69") (name "REG_BUS14") (class "Default")
      (node (ref "H8") (pin "15") (pinfunction "15_15") (pintype "input"))
      (node (ref "U7") (pin "12") (pinfunction "B6_12") (pintype "unspecified"))
    )
    (net (code "70") (name "REG_BUS15") (class "Default")
      (node (ref "H8") (pin "16") (pinfunction "16_16") (pintype "input"))
      (node (ref "U7") (pin "11") (pinfunction "B7_11") (pintype "unspecified"))
    )
    (net (code "71") (name "VCC") (class "Default")
      (node (ref "C1") (pin "1") (pinfunction "1_1") (pintype "input"))
      (node (ref "C2") (pin "1") (pinfunction "1_1") (pintype "input"))
      (node (ref "C3") (pin "1") (pinfunction "1_1") (pintype "input"))
      (node (ref "C4") (pin "1") (pinfunction "1_1") (pintype "input"))
      (node (ref "H1") (pin "1") (pinfunction "1_1") (pintype "input"))
      (node (ref "H1") (pin "2") (pinfunction "2_2") (pintype "input"))
      (node (ref "H1") (pin "3") (pinfunction "3_3") (pintype "input"))
      (node (ref "H1") (pin "4") (pinfunction "4_4") (pintype "input"))
      (node (ref "H1") (pin "5") (pinfunction "5_5") (pintype "input"))
      (node (ref "H1") (pin "6") (pinfunction "6_6") (pintype "input"))
      (node (ref "H6") (pin "1") (pinfunction "1_1") (pintype "unspecified"))
      (node (ref "H6") (pin "2") (pinfunction "2_2") (pintype "unspecified"))
      (node (ref "Q1") (pin "3") (pinfunction "C_3") (pintype "unspecified"))
      (node (ref "U5") (pin "20") (pinfunction "VCC_20") (pintype "unspecified"))
      (node (ref "U6") (pin "20") (pinfunction "VCC_20") (pintype "unspecified"))
      (node (ref "U7") (pin "1") (pinfunction "DIR_1") (pintype "unspecified"))
      (node (ref "U7") (pin "20") (pinfunction "VCC_20") (pintype "unspecified"))
      (node (ref "U8") (pin "1") (pinfunction "DIR_1") (pintype "unspecified"))
      (node (ref "U8") (pin "20") (pinfunction "VCC_20") (pintype "unspecified"))
    )
    (net (code "72") (name "unconnected-(H3-Pad1)") (class "Default")
      (node (ref "H3") (pin "1") (pinfunction "1_1") (pintype "input+no_connect"))
    )
    (net (code "73") (name "unconnected-(H3-Pad2)") (class "Default")
      (node (ref "H3") (pin "2") (pinfunction "2_2") (pintype "input+no_connect"))
    )
    (net (code "74") (name "unconnected-(H3-Pad3)") (class "Default")
      (node (ref "H3") (pin "3") (pinfunction "3_3") (pintype "input+no_connect"))
    )
    (net (code "75") (name "unconnected-(H3-Pad4)") (class "Default")
      (node (ref "H3") (pin "4") (pinfunction "4_4") (pintype "input+no_connect"))
    )
    (net (code "76") (name "unconnected-(H3-Pad5)") (class "Default")
      (node (ref "H3") (pin "5") (pinfunction "5_5") (pintype "input+no_connect"))
    )
    (net (code "77") (name "unconnected-(H3-Pad6)") (class "Default")
      (node (ref "H3") (pin "6") (pinfunction "6_6") (pintype "input+no_connect"))
    )
    (net (code "78") (name "unconnected-(H4-Pad1)") (class "Default")
      (node (ref "H4") (pin "1") (pinfunction "1_1") (pintype "input+no_connect"))
    )
    (net (code "79") (name "unconnected-(H4-Pad2)") (class "Default")
      (node (ref "H4") (pin "2") (pinfunction "2_2") (pintype "input+no_connect"))
    )
    (net (code "80") (name "unconnected-(H4-Pad3)") (class "Default")
      (node (ref "H4") (pin "3") (pinfunction "3_3") (pintype "input+no_connect"))
    )
    (net (code "81") (name "unconnected-(H4-Pad4)") (class "Default")
      (node (ref "H4") (pin "4") (pinfunction "4_4") (pintype "input+no_connect"))
    )
    (net (code "82") (name "unconnected-(H4-Pad5)") (class "Default")
      (node (ref "H4") (pin "5") (pinfunction "5_5") (pintype "input+no_connect"))
    )
    (net (code "83") (name "unconnected-(H4-Pad6)") (class "Default")
      (node (ref "H4") (pin "6") (pinfunction "6_6") (pintype "input+no_connect"))
    )
    (net (code "84") (name "unconnected-(H5-Pad3)") (class "Default")
      (node (ref "H5") (pin "3") (pinfunction "3_3") (pintype "unspecified+no_connect"))
    )
    (net (code "85") (name "unconnected-(J1-Pad2)") (class "Default")
      (node (ref "J1") (pin "2") (pinfunction "2_2") (pintype "bidirectional+no_connect"))
    )
    (net (code "86") (name "unconnected-(J1-Pad3)") (class "Default")
      (node (ref "J1") (pin "3") (pinfunction "3_3") (pintype "bidirectional+no_connect"))
    )
    (net (code "87") (name "unconnected-(J1-PadMH1)") (class "Default")
      (node (ref "J1") (pin "MH1") (pinfunction "MH1_MH1") (pintype "bidirectional+no_connect"))
    )
    (net (code "88") (name "unconnected-(J1-PadMH2)") (class "Default")
      (node (ref "J1") (pin "MH2") (pinfunction "MH2_MH2") (pintype "bidirectional+no_connect"))
    )
    (net (code "89") (name "unconnected-(U1-A0-Pad2)") (class "Default")
      (node (ref "U1") (pin "2") (pinfunction "A0_2") (pintype "input+no_connect"))
    )
    (net (code "90") (name "unconnected-(U1-A1-Pad23)") (class "Default")
      (node (ref "U1") (pin "23") (pinfunction "A1_23") (pintype "input+no_connect"))
    )
    (net (code "91") (name "unconnected-(U1-A2-Pad21)") (class "Default")
      (node (ref "U1") (pin "21") (pinfunction "A2_21") (pintype "input+no_connect"))
    )
    (net (code "92") (name "unconnected-(U1-A3-Pad19)") (class "Default")
      (node (ref "U1") (pin "19") (pinfunction "A3_19") (pintype "input+no_connect"))
    )
    (net (code "93") (name "unconnected-(U1-A=B-Pad14)") (class "Default")
      (node (ref "U1") (pin "14") (pinfunction "A=B_14") (pintype "output+no_connect"))
    )
    (net (code "94") (name "unconnected-(U1-B0-Pad1)") (class "Default")
      (node (ref "U1") (pin "1") (pinfunction "B0_1") (pintype "input+no_connect"))
    )
    (net (code "95") (name "unconnected-(U1-B1-Pad22)") (class "Default")
      (node (ref "U1") (pin "22") (pinfunction "B1_22") (pintype "input+no_connect"))
    )
    (net (code "96") (name "unconnected-(U1-B2-Pad20)") (class "Default")
      (node (ref "U1") (pin "20") (pinfunction "B2_20") (pintype "input+no_connect"))
    )
    (net (code "97") (name "unconnected-(U1-B3-Pad18)") (class "Default")
      (node (ref "U1") (pin "18") (pinfunction "B3_18") (pintype "input+no_connect"))
    )
    (net (code "98") (name "unconnected-(U1-Cn+4-Pad16)") (class "Default")
      (node (ref "U1") (pin "16") (pinfunction "Cn+4_16") (pintype "output+no_connect"))
    )
    (net (code "99") (name "unconnected-(U1-Cn-Pad7)") (class "Default")
      (node (ref "U1") (pin "7") (pinfunction "Cn_7") (pintype "input+no_connect"))
    )
    (net (code "100") (name "unconnected-(U1-F0-Pad9)") (class "Default")
      (node (ref "U1") (pin "9") (pinfunction "F0_9") (pintype "output+no_connect"))
    )
    (net (code "101") (name "unconnected-(U1-F1-Pad10)") (class "Default")
      (node (ref "U1") (pin "10") (pinfunction "F1_10") (pintype "output+no_connect"))
    )
    (net (code "102") (name "unconnected-(U1-F2-Pad11)") (class "Default")
      (node (ref "U1") (pin "11") (pinfunction "F2_11") (pintype "output+no_connect"))
    )
    (net (code "103") (name "unconnected-(U1-F3-Pad13)") (class "Default")
      (node (ref "U1") (pin "13") (pinfunction "F3_13") (pintype "output+no_connect"))
    )
    (net (code "104") (name "unconnected-(U1-GND-Pad12)") (class "Default")
      (node (ref "U1") (pin "12") (pinfunction "GND_12") (pintype "bidirectional"))
    )
    (net (code "105") (name "unconnected-(U1-M-Pad8)") (class "Default")
      (node (ref "U1") (pin "8") (pinfunction "M_8") (pintype "input+no_connect"))
    )
    (net (code "106") (name "unconnected-(U1-S0-Pad6)") (class "Default")
      (node (ref "U1") (pin "6") (pinfunction "S0_6") (pintype "input+no_connect"))
    )
    (net (code "107") (name "unconnected-(U1-S1-Pad5)") (class "Default")
      (node (ref "U1") (pin "5") (pinfunction "S1_5") (pintype "input+no_connect"))
    )
    (net (code "108") (name "unconnected-(U1-S2-Pad4)") (class "Default")
      (node (ref "U1") (pin "4") (pinfunction "S2_4") (pintype "input+no_connect"))
    )
    (net (code "109") (name "unconnected-(U1-S3-Pad3)") (class "Default")
      (node (ref "U1") (pin "3") (pinfunction "S3_3") (pintype "input+no_connect"))
    )
    (net (code "110") (name "unconnected-(U1-VCC-Pad24)") (class "Default")
      (node (ref "U1") (pin "24") (pinfunction "VCC_24") (pintype "bidirectional"))
    )
    (net (code "111") (name "unconnected-(U1-X-Pad15)") (class "Default")
      (node (ref "U1") (pin "15") (pinfunction "X_15") (pintype "output+no_connect"))
    )
    (net (code "112") (name "unconnected-(U1-Y-Pad17)") (class "Default")
      (node (ref "U1") (pin "17") (pinfunction "Y_17") (pintype "output+no_connect"))
    )
    (net (code "113") (name "unconnected-(U2-A0-Pad2)") (class "Default")
      (node (ref "U2") (pin "2") (pinfunction "A0_2") (pintype "input+no_connect"))
    )
    (net (code "114") (name "unconnected-(U2-A1-Pad23)") (class "Default")
      (node (ref "U2") (pin "23") (pinfunction "A1_23") (pintype "input+no_connect"))
    )
    (net (code "115") (name "unconnected-(U2-A2-Pad21)") (class "Default")
      (node (ref "U2") (pin "21") (pinfunction "A2_21") (pintype "input+no_connect"))
    )
    (net (code "116") (name "unconnected-(U2-A3-Pad19)") (class "Default")
      (node (ref "U2") (pin "19") (pinfunction "A3_19") (pintype "input+no_connect"))
    )
    (net (code "117") (name "unconnected-(U2-A=B-Pad14)") (class "Default")
      (node (ref "U2") (pin "14") (pinfunction "A=B_14") (pintype "output+no_connect"))
    )
    (net (code "118") (name "unconnected-(U2-B0-Pad1)") (class "Default")
      (node (ref "U2") (pin "1") (pinfunction "B0_1") (pintype "input+no_connect"))
    )
    (net (code "119") (name "unconnected-(U2-B1-Pad22)") (class "Default")
      (node (ref "U2") (pin "22") (pinfunction "B1_22") (pintype "input+no_connect"))
    )
    (net (code "120") (name "unconnected-(U2-B2-Pad20)") (class "Default")
      (node (ref "U2") (pin "20") (pinfunction "B2_20") (pintype "input+no_connect"))
    )
    (net (code "121") (name "unconnected-(U2-B3-Pad18)") (class "Default")
      (node (ref "U2") (pin "18") (pinfunction "B3_18") (pintype "input+no_connect"))
    )
    (net (code "122") (name "unconnected-(U2-Cn+4-Pad16)") (class "Default")
      (node (ref "U2") (pin "16") (pinfunction "Cn+4_16") (pintype "output+no_connect"))
    )
    (net (code "123") (name "unconnected-(U2-Cn-Pad7)") (class "Default")
      (node (ref "U2") (pin "7") (pinfunction "Cn_7") (pintype "input+no_connect"))
    )
    (net (code "124") (name "unconnected-(U2-F0-Pad9)") (class "Default")
      (node (ref "U2") (pin "9") (pinfunction "F0_9") (pintype "output+no_connect"))
    )
    (net (code "125") (name "unconnected-(U2-F1-Pad10)") (class "Default")
      (node (ref "U2") (pin "10") (pinfunction "F1_10") (pintype "output+no_connect"))
    )
    (net (code "126") (name "unconnected-(U2-F2-Pad11)") (class "Default")
      (node (ref "U2") (pin "11") (pinfunction "F2_11") (pintype "output+no_connect"))
    )
    (net (code "127") (name "unconnected-(U2-F3-Pad13)") (class "Default")
      (node (ref "U2") (pin "13") (pinfunction "F3_13") (pintype "output+no_connect"))
    )
    (net (code "128") (name "unconnected-(U2-GND-Pad12)") (class "Default")
      (node (ref "U2") (pin "12") (pinfunction "GND_12") (pintype "bidirectional"))
    )
    (net (code "129") (name "unconnected-(U2-M-Pad8)") (class "Default")
      (node (ref "U2") (pin "8") (pinfunction "M_8") (pintype "input+no_connect"))
    )
    (net (code "130") (name "unconnected-(U2-S0-Pad6)") (class "Default")
      (node (ref "U2") (pin "6") (pinfunction "S0_6") (pintype "input+no_connect"))
    )
    (net (code "131") (name "unconnected-(U2-S1-Pad5)") (class "Default")
      (node (ref "U2") (pin "5") (pinfunction "S1_5") (pintype "input+no_connect"))
    )
    (net (code "132") (name "unconnected-(U2-S2-Pad4)") (class "Default")
      (node (ref "U2") (pin "4") (pinfunction "S2_4") (pintype "input+no_connect"))
    )
    (net (code "133") (name "unconnected-(U2-S3-Pad3)") (class "Default")
      (node (ref "U2") (pin "3") (pinfunction "S3_3") (pintype "input+no_connect"))
    )
    (net (code "134") (name "unconnected-(U2-VCC-Pad24)") (class "Default")
      (node (ref "U2") (pin "24") (pinfunction "VCC_24") (pintype "bidirectional"))
    )
    (net (code "135") (name "unconnected-(U2-X-Pad15)") (class "Default")
      (node (ref "U2") (pin "15") (pinfunction "X_15") (pintype "output+no_connect"))
    )
    (net (code "136") (name "unconnected-(U2-Y-Pad17)") (class "Default")
      (node (ref "U2") (pin "17") (pinfunction "Y_17") (pintype "output+no_connect"))
    )
    (net (code "137") (name "unconnected-(U3-A0-Pad2)") (class "Default")
      (node (ref "U3") (pin "2") (pinfunction "A0_2") (pintype "input+no_connect"))
    )
    (net (code "138") (name "unconnected-(U3-A1-Pad23)") (class "Default")
      (node (ref "U3") (pin "23") (pinfunction "A1_23") (pintype "input+no_connect"))
    )
    (net (code "139") (name "unconnected-(U3-A2-Pad21)") (class "Default")
      (node (ref "U3") (pin "21") (pinfunction "A2_21") (pintype "input+no_connect"))
    )
    (net (code "140") (name "unconnected-(U3-A3-Pad19)") (class "Default")
      (node (ref "U3") (pin "19") (pinfunction "A3_19") (pintype "input+no_connect"))
    )
    (net (code "141") (name "unconnected-(U3-A=B-Pad14)") (class "Default")
      (node (ref "U3") (pin "14") (pinfunction "A=B_14") (pintype "output+no_connect"))
    )
    (net (code "142") (name "unconnected-(U3-B0-Pad1)") (class "Default")
      (node (ref "U3") (pin "1") (pinfunction "B0_1") (pintype "input+no_connect"))
    )
    (net (code "143") (name "unconnected-(U3-B1-Pad22)") (class "Default")
      (node (ref "U3") (pin "22") (pinfunction "B1_22") (pintype "input+no_connect"))
    )
    (net (code "144") (name "unconnected-(U3-B2-Pad20)") (class "Default")
      (node (ref "U3") (pin "20") (pinfunction "B2_20") (pintype "input+no_connect"))
    )
    (net (code "145") (name "unconnected-(U3-B3-Pad18)") (class "Default")
      (node (ref "U3") (pin "18") (pinfunction "B3_18") (pintype "input+no_connect"))
    )
    (net (code "146") (name "unconnected-(U3-Cn+4-Pad16)") (class "Default")
      (node (ref "U3") (pin "16") (pinfunction "Cn+4_16") (pintype "output+no_connect"))
    )
    (net (code "147") (name "unconnected-(U3-Cn-Pad7)") (class "Default")
      (node (ref "U3") (pin "7") (pinfunction "Cn_7") (pintype "input+no_connect"))
    )
    (net (code "148") (name "unconnected-(U3-F0-Pad9)") (class "Default")
      (node (ref "U3") (pin "9") (pinfunction "F0_9") (pintype "output+no_connect"))
    )
    (net (code "149") (name "unconnected-(U3-F1-Pad10)") (class "Default")
      (node (ref "U3") (pin "10") (pinfunction "F1_10") (pintype "output+no_connect"))
    )
    (net (code "150") (name "unconnected-(U3-F2-Pad11)") (class "Default")
      (node (ref "U3") (pin "11") (pinfunction "F2_11") (pintype "output+no_connect"))
    )
    (net (code "151") (name "unconnected-(U3-F3-Pad13)") (class "Default")
      (node (ref "U3") (pin "13") (pinfunction "F3_13") (pintype "output+no_connect"))
    )
    (net (code "152") (name "unconnected-(U3-GND-Pad12)") (class "Default")
      (node (ref "U3") (pin "12") (pinfunction "GND_12") (pintype "bidirectional"))
    )
    (net (code "153") (name "unconnected-(U3-M-Pad8)") (class "Default")
      (node (ref "U3") (pin "8") (pinfunction "M_8") (pintype "input+no_connect"))
    )
    (net (code "154") (name "unconnected-(U3-S0-Pad6)") (class "Default")
      (node (ref "U3") (pin "6") (pinfunction "S0_6") (pintype "input+no_connect"))
    )
    (net (code "155") (name "unconnected-(U3-S1-Pad5)") (class "Default")
      (node (ref "U3") (pin "5") (pinfunction "S1_5") (pintype "input+no_connect"))
    )
    (net (code "156") (name "unconnected-(U3-S2-Pad4)") (class "Default")
      (node (ref "U3") (pin "4") (pinfunction "S2_4") (pintype "input+no_connect"))
    )
    (net (code "157") (name "unconnected-(U3-S3-Pad3)") (class "Default")
      (node (ref "U3") (pin "3") (pinfunction "S3_3") (pintype "input+no_connect"))
    )
    (net (code "158") (name "unconnected-(U3-VCC-Pad24)") (class "Default")
      (node (ref "U3") (pin "24") (pinfunction "VCC_24") (pintype "bidirectional"))
    )
    (net (code "159") (name "unconnected-(U3-X-Pad15)") (class "Default")
      (node (ref "U3") (pin "15") (pinfunction "X_15") (pintype "output+no_connect"))
    )
    (net (code "160") (name "unconnected-(U3-Y-Pad17)") (class "Default")
      (node (ref "U3") (pin "17") (pinfunction "Y_17") (pintype "output+no_connect"))
    )
    (net (code "161") (name "unconnected-(U4-A0-Pad2)") (class "Default")
      (node (ref "U4") (pin "2") (pinfunction "A0_2") (pintype "input+no_connect"))
    )
    (net (code "162") (name "unconnected-(U4-A1-Pad23)") (class "Default")
      (node (ref "U4") (pin "23") (pinfunction "A1_23") (pintype "input+no_connect"))
    )
    (net (code "163") (name "unconnected-(U4-A2-Pad21)") (class "Default")
      (node (ref "U4") (pin "21") (pinfunction "A2_21") (pintype "input+no_connect"))
    )
    (net (code "164") (name "unconnected-(U4-A3-Pad19)") (class "Default")
      (node (ref "U4") (pin "19") (pinfunction "A3_19") (pintype "input+no_connect"))
    )
    (net (code "165") (name "unconnected-(U4-A=B-Pad14)") (class "Default")
      (node (ref "U4") (pin "14") (pinfunction "A=B_14") (pintype "output+no_connect"))
    )
    (net (code "166") (name "unconnected-(U4-B0-Pad1)") (class "Default")
      (node (ref "U4") (pin "1") (pinfunction "B0_1") (pintype "input+no_connect"))
    )
    (net (code "167") (name "unconnected-(U4-B1-Pad22)") (class "Default")
      (node (ref "U4") (pin "22") (pinfunction "B1_22") (pintype "input+no_connect"))
    )
    (net (code "168") (name "unconnected-(U4-B2-Pad20)") (class "Default")
      (node (ref "U4") (pin "20") (pinfunction "B2_20") (pintype "input+no_connect"))
    )
    (net (code "169") (name "unconnected-(U4-B3-Pad18)") (class "Default")
      (node (ref "U4") (pin "18") (pinfunction "B3_18") (pintype "input+no_connect"))
    )
    (net (code "170") (name "unconnected-(U4-Cn+4-Pad16)") (class "Default")
      (node (ref "U4") (pin "16") (pinfunction "Cn+4_16") (pintype "output+no_connect"))
    )
    (net (code "171") (name "unconnected-(U4-Cn-Pad7)") (class "Default")
      (node (ref "U4") (pin "7") (pinfunction "Cn_7") (pintype "input+no_connect"))
    )
    (net (code "172") (name "unconnected-(U4-F0-Pad9)") (class "Default")
      (node (ref "U4") (pin "9") (pinfunction "F0_9") (pintype "output+no_connect"))
    )
    (net (code "173") (name "unconnected-(U4-F1-Pad10)") (class "Default")
      (node (ref "U4") (pin "10") (pinfunction "F1_10") (pintype "output+no_connect"))
    )
    (net (code "174") (name "unconnected-(U4-F2-Pad11)") (class "Default")
      (node (ref "U4") (pin "11") (pinfunction "F2_11") (pintype "output+no_connect"))
    )
    (net (code "175") (name "unconnected-(U4-F3-Pad13)") (class "Default")
      (node (ref "U4") (pin "13") (pinfunction "F3_13") (pintype "output+no_connect"))
    )
    (net (code "176") (name "unconnected-(U4-GND-Pad12)") (class "Default")
      (node (ref "U4") (pin "12") (pinfunction "GND_12") (pintype "bidirectional"))
    )
    (net (code "177") (name "unconnected-(U4-M-Pad8)") (class "Default")
      (node (ref "U4") (pin "8") (pinfunction "M_8") (pintype "input+no_connect"))
    )
    (net (code "178") (name "unconnected-(U4-S0-Pad6)") (class "Default")
      (node (ref "U4") (pin "6") (pinfunction "S0_6") (pintype "input+no_connect"))
    )
    (net (code "179") (name "unconnected-(U4-S1-Pad5)") (class "Default")
      (node (ref "U4") (pin "5") (pinfunction "S1_5") (pintype "input+no_connect"))
    )
    (net (code "180") (name "unconnected-(U4-S2-Pad4)") (class "Default")
      (node (ref "U4") (pin "4") (pinfunction "S2_4") (pintype "input+no_connect"))
    )
    (net (code "181") (name "unconnected-(U4-S3-Pad3)") (class "Default")
      (node (ref "U4") (pin "3") (pinfunction "S3_3") (pintype "input+no_connect"))
    )
    (net (code "182") (name "unconnected-(U4-VCC-Pad24)") (class "Default")
      (node (ref "U4") (pin "24") (pinfunction "VCC_24") (pintype "bidirectional"))
    )
    (net (code "183") (name "unconnected-(U4-X-Pad15)") (class "Default")
      (node (ref "U4") (pin "15") (pinfunction "X_15") (pintype "output+no_connect"))
    )
    (net (code "184") (name "unconnected-(U4-Y-Pad17)") (class "Default")
      (node (ref "U4") (pin "17") (pinfunction "Y_17") (pintype "output+no_connect"))
    )
    (net (code "185") (name "{slash}EN") (class "Default")
      (node (ref "H5") (pin "1") (pinfunction "1_1") (pintype "unspecified"))
      (node (ref "U5") (pin "1") (pinfunction "CLKEN#_1") (pintype "unspecified"))
      (node (ref "U6") (pin "1") (pinfunction "CLKEN#_1") (pintype "unspecified"))
    )
    (net (code "186") (name "{slash}OE") (class "Default")
      (node (ref "H5") (pin "2") (pinfunction "2_2") (pintype "unspecified"))
      (node (ref "U7") (pin "19") (pinfunction "OE_19") (pintype "unspecified"))
      (node (ref "U8") (pin "19") (pinfunction "OE_19") (pintype "unspecified"))
    )
  )
)
